# ECUTeen3_5_rev_A_20180306.net
KiCad netlist of a schematic drawn in EAGLE
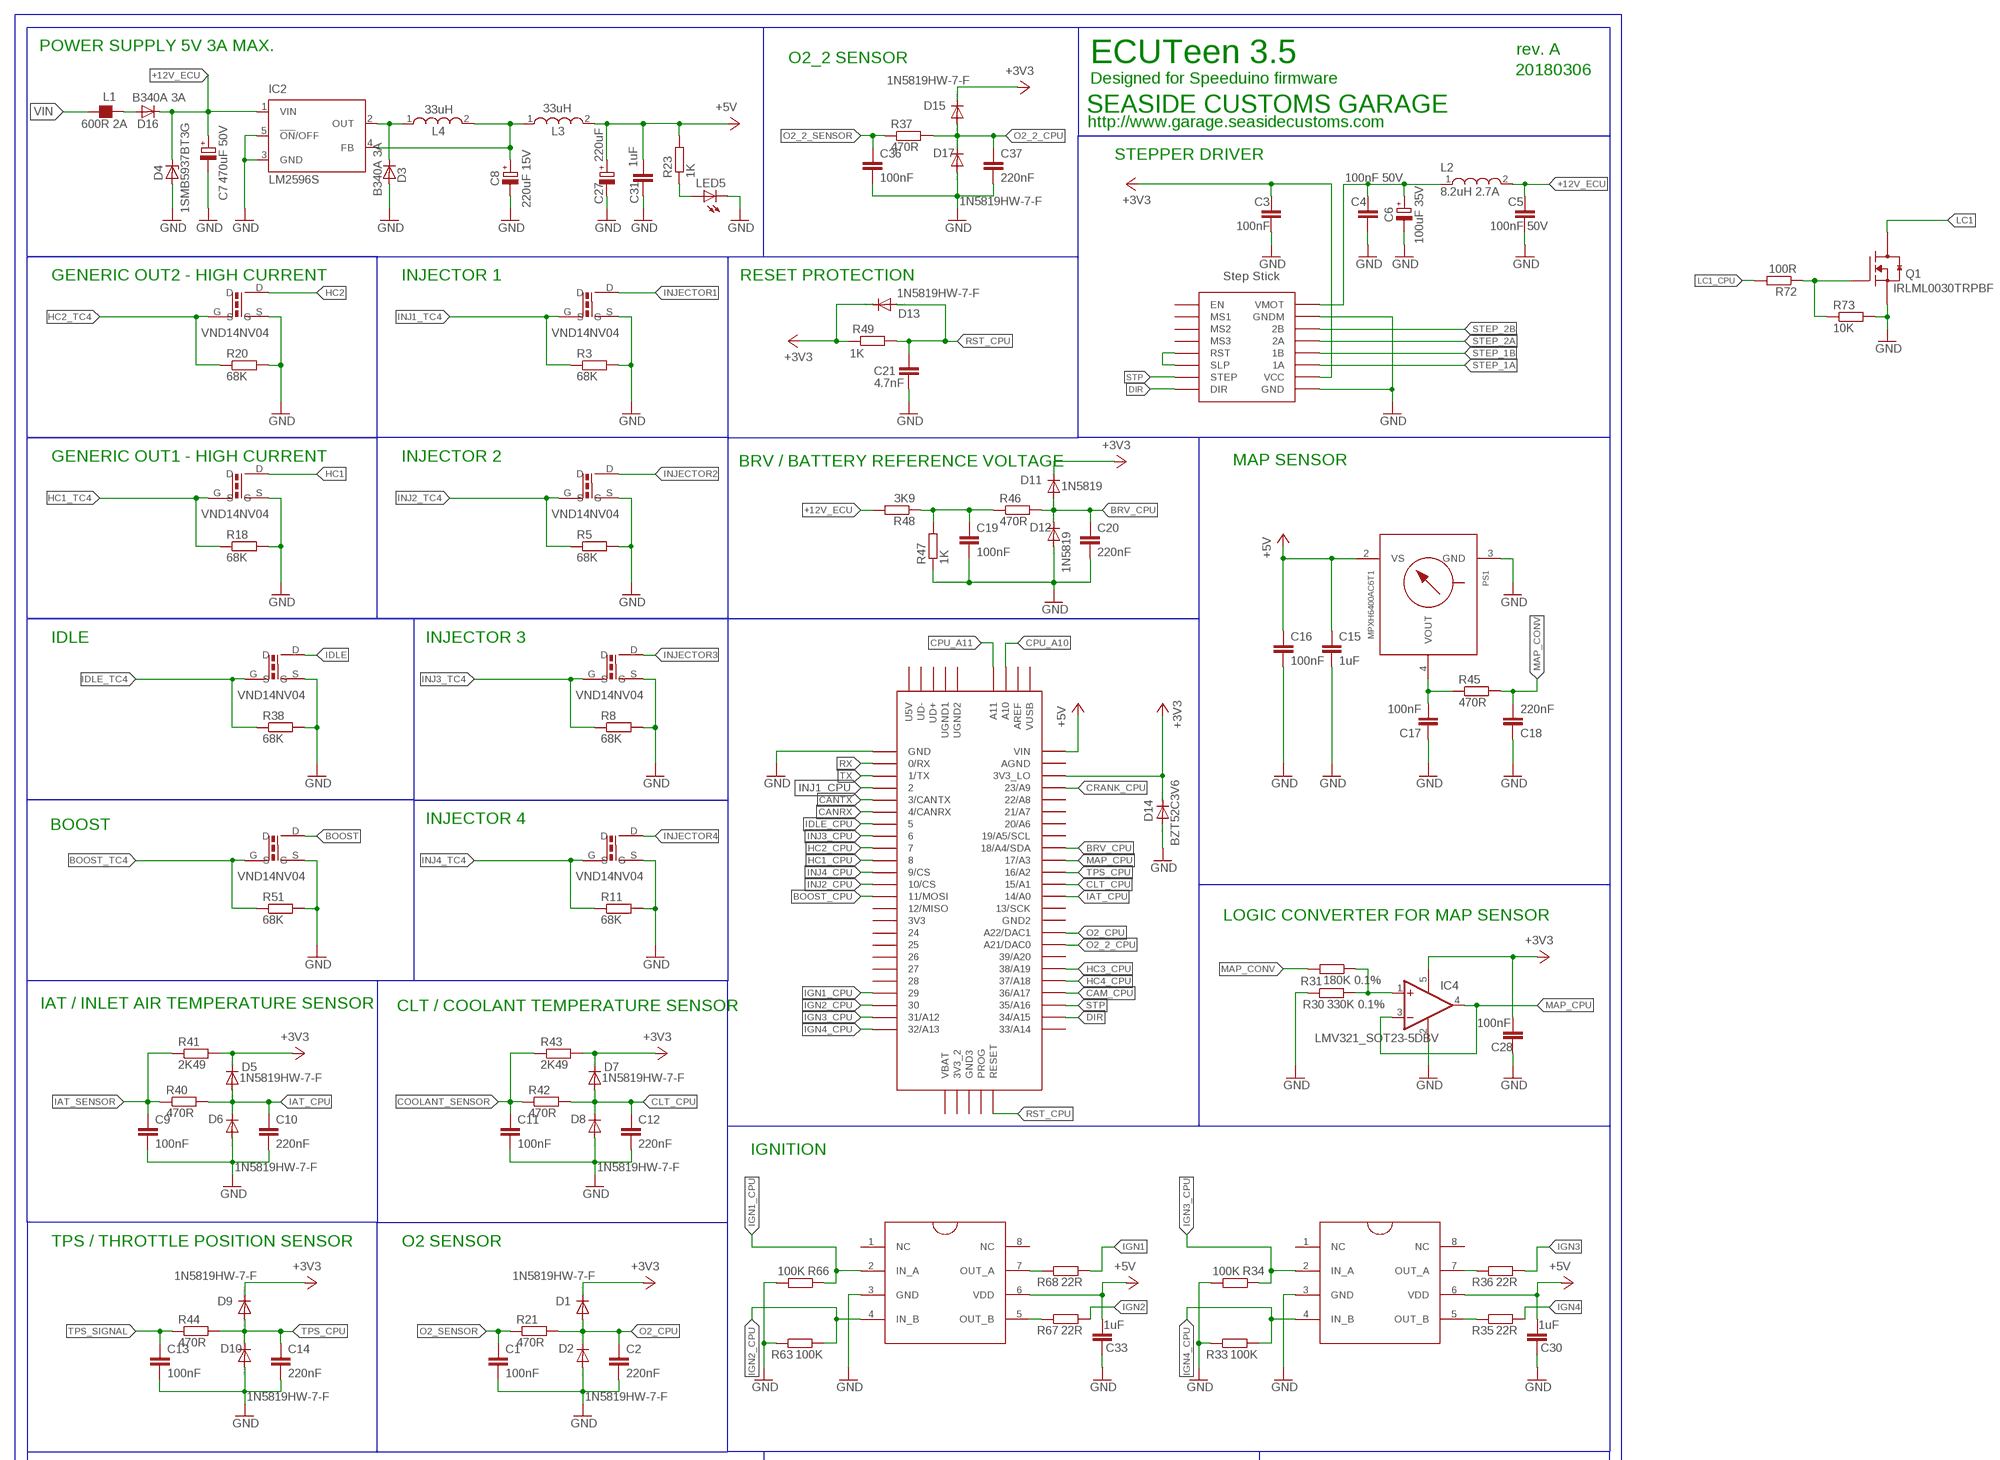
[diagram p0: schematic, sheet 1, part 1 of 2]
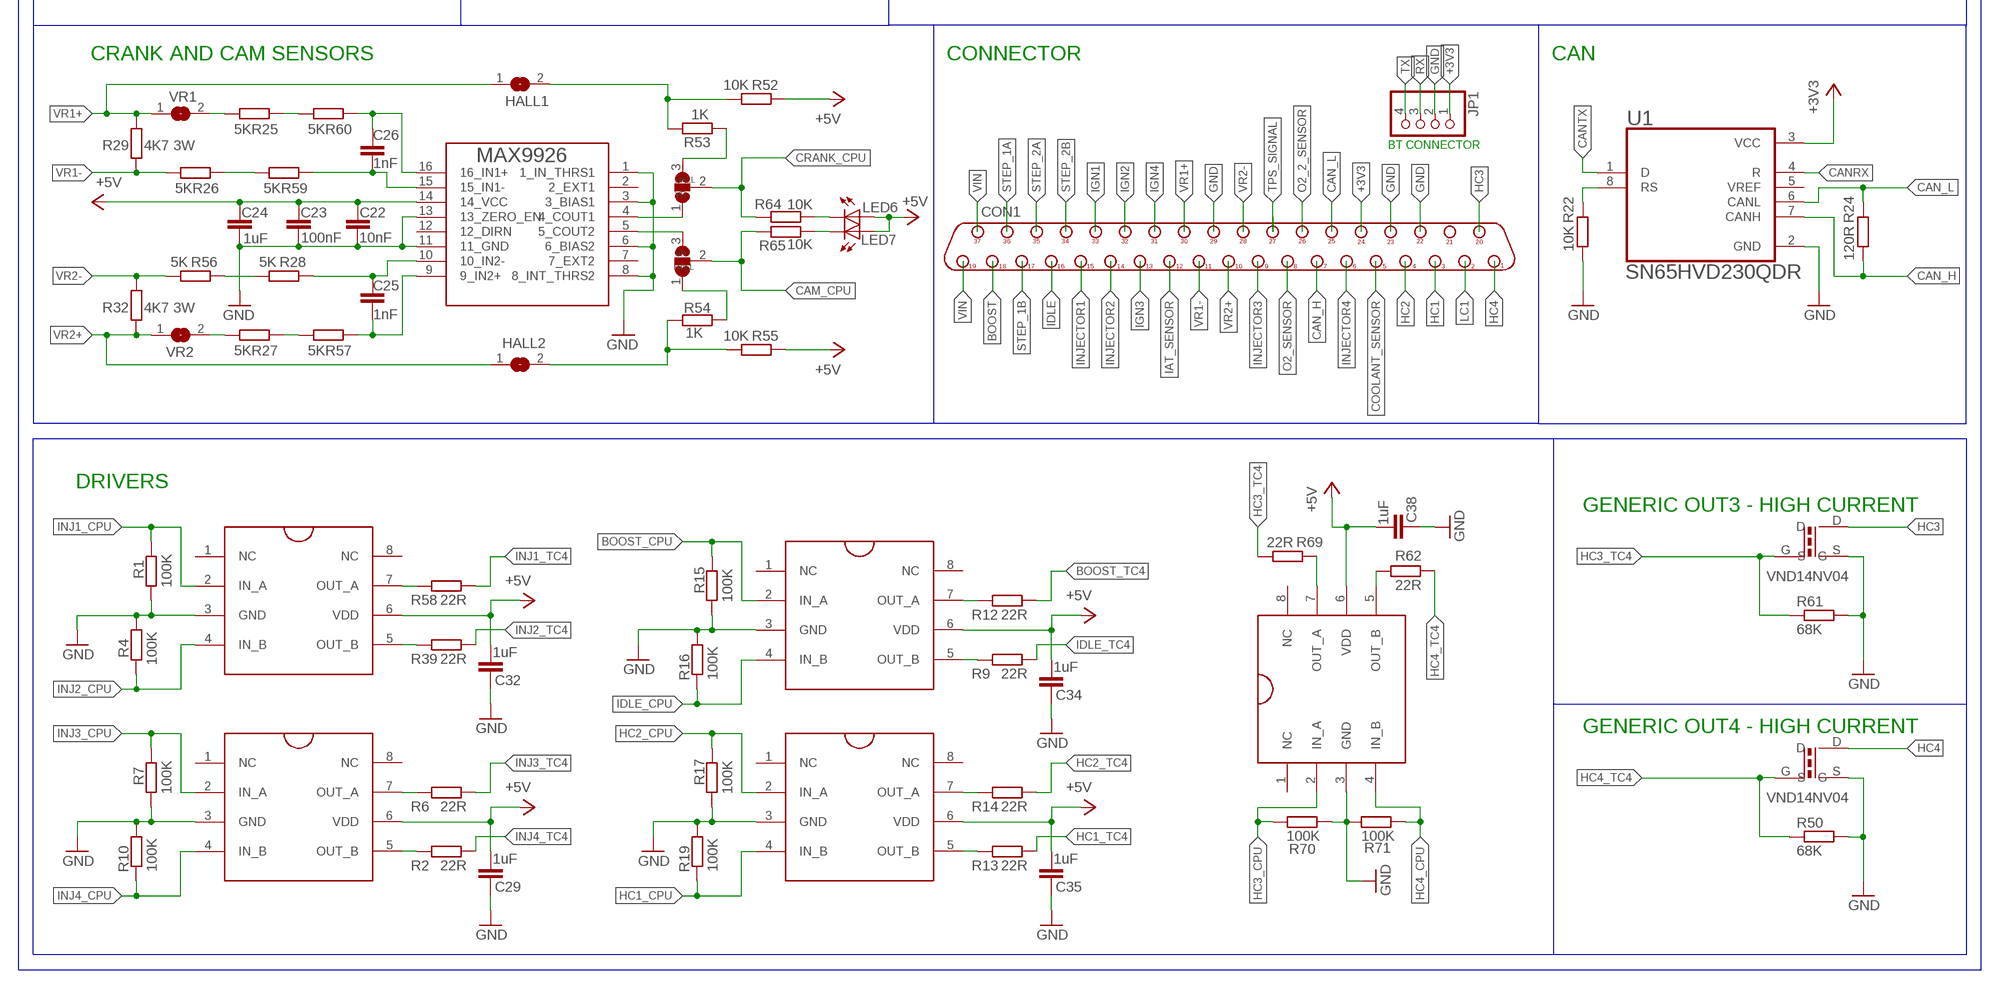
[diagram p1: schematic, sheet 1, part 2 of 2]

(export (version "E")
  (design (tool "Eeschema 10.0.6"))
  (components
    (comp (ref "C1")
      (value "100nF")
      (footprint "eagle-import:C0805")
      (libsource (lib "eagle-import") (part "C-EUC0805"))
    )
    (comp (ref "C2")
      (value "220nF")
      (footprint "eagle-import:C0805")
      (libsource (lib "eagle-import") (part "C-EUC0805"))
    )
    (comp (ref "C3")
      (value "100nF")
      (footprint "eagle-import:C0805")
      (libsource (lib "eagle-import") (part "C-EUC0805"))
    )
    (comp (ref "C4")
      (value "100nF 50V")
      (footprint "eagle-import:C0805")
      (libsource (lib "eagle-import") (part "C-EUC0805"))
    )
    (comp (ref "C5")
      (value "100nF 50V")
      (footprint "eagle-import:C0805")
      (libsource (lib "eagle-import") (part "C-EUC0805"))
    )
    (comp (ref "C6")
      (value "100uF 35V")
      (footprint "eagle-import:PANASONIC_D")
      (libsource (lib "eagle-import") (part "CPOL-EUD"))
    )
    (comp (ref "C7")
      (value "470uF 50V")
      (footprint "eagle-import:PANASONIC_D")
      (libsource (lib "eagle-import") (part "CPOL-EUD"))
    )
    (comp (ref "C8")
      (value "220uF 15V")
      (footprint "eagle-import:PANASONIC_D")
      (libsource (lib "eagle-import") (part "CPOL-EUD"))
    )
    (comp (ref "C9")
      (value "100nF")
      (footprint "eagle-import:C0805")
      (libsource (lib "eagle-import") (part "C-EUC0805"))
    )
    (comp (ref "C10")
      (value "220nF")
      (footprint "eagle-import:C0805")
      (libsource (lib "eagle-import") (part "C-EUC0805"))
    )
    (comp (ref "C11")
      (value "100nF")
      (footprint "eagle-import:C0805")
      (libsource (lib "eagle-import") (part "C-EUC0805"))
    )
    (comp (ref "C12")
      (value "220nF")
      (footprint "eagle-import:C0805")
      (libsource (lib "eagle-import") (part "C-EUC0805"))
    )
    (comp (ref "C13")
      (value "100nF")
      (footprint "eagle-import:C0805")
      (libsource (lib "eagle-import") (part "C-EUC0805"))
    )
    (comp (ref "C14")
      (value "220nF")
      (footprint "eagle-import:C0805")
      (libsource (lib "eagle-import") (part "C-EUC0805"))
    )
    (comp (ref "C15")
      (value "1uF")
      (footprint "eagle-import:C0805")
      (libsource (lib "eagle-import") (part "C-EUC0805"))
    )
    (comp (ref "C16")
      (value "100nF")
      (footprint "eagle-import:C0805")
      (libsource (lib "eagle-import") (part "C-EUC0805"))
    )
    (comp (ref "C17")
      (value "100nF")
      (footprint "eagle-import:C0805")
      (libsource (lib "eagle-import") (part "C-EUC0805"))
    )
    (comp (ref "C18")
      (value "220nF")
      (footprint "eagle-import:C0805")
      (libsource (lib "eagle-import") (part "C-EUC0805"))
    )
    (comp (ref "C19")
      (value "100nF")
      (footprint "eagle-import:C0805")
      (libsource (lib "eagle-import") (part "C-EUC0805"))
    )
    (comp (ref "C20")
      (value "220nF")
      (footprint "eagle-import:C0805")
      (libsource (lib "eagle-import") (part "C-EUC0805"))
    )
    (comp (ref "C21")
      (value "4.7nF")
      (footprint "eagle-import:C0805")
      (libsource (lib "eagle-import") (part "C-EUC0805"))
    )
    (comp (ref "C22")
      (value "10nF")
      (footprint "eagle-import:C0805")
      (libsource (lib "eagle-import") (part "C-EUC0805"))
    )
    (comp (ref "C23")
      (value "100nF")
      (footprint "eagle-import:C0805")
      (libsource (lib "eagle-import") (part "C-EUC0805"))
    )
    (comp (ref "C24")
      (value "1uF")
      (footprint "eagle-import:C0805")
      (libsource (lib "eagle-import") (part "C-EUC0805"))
    )
    (comp (ref "C25")
      (value "1nF")
      (footprint "eagle-import:C0805")
      (libsource (lib "eagle-import") (part "C-EUC0805"))
    )
    (comp (ref "C26")
      (value "1nF")
      (footprint "eagle-import:C0805")
      (libsource (lib "eagle-import") (part "C-EUC0805"))
    )
    (comp (ref "C27")
      (value "220uF")
      (footprint "eagle-import:PANASONIC_D")
      (libsource (lib "eagle-import") (part "CPOL-EUD"))
    )
    (comp (ref "C28")
      (value "100nF")
      (footprint "eagle-import:C0805")
      (libsource (lib "eagle-import") (part "C-EUC0805"))
    )
    (comp (ref "C29")
      (value "1uF")
      (footprint "eagle-import:C0805")
      (libsource (lib "eagle-import") (part "C-EUC0805"))
    )
    (comp (ref "C30")
      (value "1uF")
      (footprint "eagle-import:C0805")
      (libsource (lib "eagle-import") (part "C-EUC0805"))
    )
    (comp (ref "C31")
      (value "1uF")
      (footprint "eagle-import:C0805")
      (libsource (lib "eagle-import") (part "C-EUC0805"))
    )
    (comp (ref "C32")
      (value "1uF")
      (footprint "eagle-import:C0805")
      (libsource (lib "eagle-import") (part "C-EUC0805"))
    )
    (comp (ref "C33")
      (value "1uF")
      (footprint "eagle-import:C0805")
      (libsource (lib "eagle-import") (part "C-EUC0805"))
    )
    (comp (ref "C34")
      (value "1uF")
      (footprint "eagle-import:C0805")
      (libsource (lib "eagle-import") (part "C-EUC0805"))
    )
    (comp (ref "C35")
      (value "1uF")
      (footprint "eagle-import:C0805")
      (libsource (lib "eagle-import") (part "C-EUC0805"))
    )
    (comp (ref "C36")
      (value "100nF")
      (footprint "eagle-import:C0805")
      (libsource (lib "eagle-import") (part "C-EUC0805"))
    )
    (comp (ref "C37")
      (value "220nF")
      (footprint "eagle-import:C0805")
      (libsource (lib "eagle-import") (part "C-EUC0805"))
    )
    (comp (ref "C38")
      (value "1uF")
      (footprint "eagle-import:C0805")
      (libsource (lib "eagle-import") (part "C-EUC0805"))
    )
    (comp (ref "CON1")
      (value "DB37M/90")
      (footprint "eagle-import:D-37M_90")
      (libsource (lib "eagle-import") (part "DB37M/90"))
    )
    (comp (ref "D1")
      (value "1N5819HW-7-F")
      (footprint "eagle-import:SOD123")
      (libsource (lib "eagle-import") (part "diode_DIODE-SOD123"))
    )
    (comp (ref "D2")
      (value "1N5819HW-7-F")
      (footprint "eagle-import:SOD123")
      (libsource (lib "eagle-import") (part "diode_DIODE-SOD123"))
    )
    (comp (ref "D3")
      (value "B340A 3A")
      (footprint "eagle-import:DO214AC")
      (fields (field (name "MF") "Fairchild") (field (name "MPN") "S1A"))
      (libsource (lib "eagle-import") (part "S1A"))
    )
    (comp (ref "D4")
      (value "1SMB5937BT3G")
      (footprint "eagle-import:SMB")
      (libsource (lib "eagle-import") (part "ZENER-DIODESMB"))
    )
    (comp (ref "D5")
      (value "1N5819HW-7-F")
      (footprint "eagle-import:SOD123")
      (libsource (lib "eagle-import") (part "diode_DIODE-SOD123"))
    )
    (comp (ref "D6")
      (value "1N5819HW-7-F")
      (footprint "eagle-import:SOD123")
      (libsource (lib "eagle-import") (part "diode_DIODE-SOD123"))
    )
    (comp (ref "D7")
      (value "1N5819HW-7-F")
      (footprint "eagle-import:SOD123")
      (libsource (lib "eagle-import") (part "diode_DIODE-SOD123"))
    )
    (comp (ref "D8")
      (value "1N5819HW-7-F")
      (footprint "eagle-import:SOD123")
      (libsource (lib "eagle-import") (part "diode_DIODE-SOD123"))
    )
    (comp (ref "D9")
      (value "1N5819HW-7-F")
      (footprint "eagle-import:SOD123")
      (libsource (lib "eagle-import") (part "diode_DIODE-SOD123"))
    )
    (comp (ref "D10")
      (value "1N5819HW-7-F")
      (footprint "eagle-import:SOD123")
      (libsource (lib "eagle-import") (part "diode_DIODE-SOD123"))
    )
    (comp (ref "D11")
      (value "1N5819")
      (footprint "eagle-import:SOD123")
      (libsource (lib "eagle-import") (part "diode_DIODE-SOD123"))
    )
    (comp (ref "D12")
      (value "1N5819")
      (footprint "eagle-import:SOD123")
      (libsource (lib "eagle-import") (part "diode_DIODE-SOD123"))
    )
    (comp (ref "D13")
      (value "1N5819HW-7-F")
      (footprint "eagle-import:SOD123")
      (libsource (lib "eagle-import") (part "diode_DIODE-SOD123"))
    )
    (comp (ref "D14")
      (value "BZT52C3V6")
      (footprint "eagle-import:SOD123")
      (libsource (lib "eagle-import") (part "DIODE-SOD123"))
    )
    (comp (ref "D15")
      (value "1N5819HW-7-F")
      (footprint "eagle-import:SOD123")
      (libsource (lib "eagle-import") (part "diode_DIODE-SOD123"))
    )
    (comp (ref "D16")
      (value "B340A 3A")
      (footprint "eagle-import:DO214AC")
      (fields (field (name "MF") "Fairchild") (field (name "MPN") "S1A"))
      (libsource (lib "eagle-import") (part "S1A"))
    )
    (comp (ref "D17")
      (value "1N5819HW-7-F")
      (footprint "eagle-import:SOD123")
      (libsource (lib "eagle-import") (part "diode_DIODE-SOD123"))
    )
    (comp (ref "IC2")
      (value "LM2596S")
      (footprint "eagle-import:TO263-5")
      (fields (field (name "MF") "NATIONAL SEMICONDUCTOR") (field (name "MPN") "LM2596S-ADJ/NOPB"))
      (libsource (lib "eagle-import") (part "LM2596S"))
    )
    (comp (ref "IC4")
      (value "LMV321_SOT23-5DBV")
      (footprint "eagle-import:SOT23-5")
      (libsource (lib "eagle-import") (part "LMV321_SOT23-5DBV"))
    )
    (comp (ref "JMP1")
      (value "SJ2W")
      (footprint "eagle-import:SJ_2")
      (libsource (lib "eagle-import") (part "SJ2W"))
    )
    (comp (ref "JMP2")
      (value "SJ2W")
      (footprint "eagle-import:SJ_2")
      (libsource (lib "eagle-import") (part "SJ2W"))
    )
    (comp (ref "JP1")
      (value "PINHD-1X4")
      (footprint "eagle-import:1X04")
      (libsource (lib "eagle-import") (part "PINHD-1X4"))
    )
    (comp (ref "L1")
      (value "600R 2A")
      (footprint "eagle-import:L1206")
      (libsource (lib "eagle-import") (part "FB_1206"))
    )
    (comp (ref "L2")
      (value "8.2uH 2.7A")
      (footprint "eagle-import:WE-PD_7332_7345_PLASTIC_BASE")
      (libsource (lib "eagle-import") (part "WE-PD_7332/7345_PLASTIC_BASE"))
    )
    (comp (ref "L3")
      (value "33uH")
      (footprint "eagle-import:WE-LHMI_7030_7050")
      (libsource (lib "eagle-import") (part "WE-LHMI_7030/7050"))
    )
    (comp (ref "L4")
      (value "33uH")
      (footprint "eagle-import:WE-LHMI_7030_7050")
      (libsource (lib "eagle-import") (part "WE-LHMI_7030/7050"))
    )
    (comp (ref "LED5")
      (value "LEDCHIP-LED0805")
      (footprint "eagle-import:CHIP-LED0805")
      (libsource (lib "eagle-import") (part "LEDCHIP-LED0805"))
    )
    (comp (ref "LED6")
      (value "LEDCHIP-LED0805")
      (footprint "eagle-import:CHIP-LED0805")
      (libsource (lib "eagle-import") (part "LEDCHIP-LED0805"))
    )
    (comp (ref "LED7")
      (value "LEDCHIP-LED0805")
      (footprint "eagle-import:CHIP-LED0805")
      (libsource (lib "eagle-import") (part "LEDCHIP-LED0805"))
    )
    (comp (ref "PS1")
      (value "MPXH6400AC6T1")
      (footprint "eagle-import:1317A")
      (libsource (lib "eagle-import") (part "MPXH6400AC6T1"))
    )
    (comp (ref "Q1")
      (value "IRLML0030TRPBF")
      (footprint "eagle-import:SOT95P280X135-3N")
      (libsource (lib "eagle-import") (part "MOSFET-NCH_SOT-23"))
    )
    (comp (ref "R1")
      (value "100K")
      (footprint "eagle-import:R0805")
      (libsource (lib "eagle-import") (part "R-EU_R0805"))
    )
    (comp (ref "R2")
      (value "22R")
      (footprint "eagle-import:R0805")
      (libsource (lib "eagle-import") (part "R-EU_R0805"))
    )
    (comp (ref "R3")
      (value "68K")
      (footprint "eagle-import:R0805")
      (libsource (lib "eagle-import") (part "R-EU_R0805"))
    )
    (comp (ref "R4")
      (value "100K")
      (footprint "eagle-import:R0805")
      (libsource (lib "eagle-import") (part "R-EU_R0805"))
    )
    (comp (ref "R5")
      (value "68K")
      (footprint "eagle-import:R0805")
      (libsource (lib "eagle-import") (part "R-EU_R0805"))
    )
    (comp (ref "R6")
      (value "22R")
      (footprint "eagle-import:R0805")
      (libsource (lib "eagle-import") (part "R-EU_R0805"))
    )
    (comp (ref "R7")
      (value "100K")
      (footprint "eagle-import:R0805")
      (libsource (lib "eagle-import") (part "R-EU_R0805"))
    )
    (comp (ref "R8")
      (value "68K")
      (footprint "eagle-import:R0805")
      (libsource (lib "eagle-import") (part "R-EU_R0805"))
    )
    (comp (ref "R9")
      (value "22R")
      (footprint "eagle-import:R0805")
      (libsource (lib "eagle-import") (part "R-EU_R0805"))
    )
    (comp (ref "R10")
      (value "100K")
      (footprint "eagle-import:R0805")
      (libsource (lib "eagle-import") (part "R-EU_R0805"))
    )
    (comp (ref "R11")
      (value "68K")
      (footprint "eagle-import:R0805")
      (libsource (lib "eagle-import") (part "R-EU_R0805"))
    )
    (comp (ref "R12")
      (value "22R")
      (footprint "eagle-import:R0805")
      (libsource (lib "eagle-import") (part "R-EU_R0805"))
    )
    (comp (ref "R13")
      (value "22R")
      (footprint "eagle-import:R0805")
      (libsource (lib "eagle-import") (part "R-EU_R0805"))
    )
    (comp (ref "R14")
      (value "22R")
      (footprint "eagle-import:R0805")
      (libsource (lib "eagle-import") (part "R-EU_R0805"))
    )
    (comp (ref "R15")
      (value "100K")
      (footprint "eagle-import:R0805")
      (libsource (lib "eagle-import") (part "R-EU_R0805"))
    )
    (comp (ref "R16")
      (value "100K")
      (footprint "eagle-import:R0805")
      (libsource (lib "eagle-import") (part "R-EU_R0805"))
    )
    (comp (ref "R17")
      (value "100K")
      (footprint "eagle-import:R0805")
      (libsource (lib "eagle-import") (part "R-EU_R0805"))
    )
    (comp (ref "R18")
      (value "68K")
      (footprint "eagle-import:R0805")
      (libsource (lib "eagle-import") (part "R-EU_R0805"))
    )
    (comp (ref "R19")
      (value "100K")
      (footprint "eagle-import:R0805")
      (libsource (lib "eagle-import") (part "R-EU_R0805"))
    )
    (comp (ref "R20")
      (value "68K")
      (footprint "eagle-import:R0805")
      (libsource (lib "eagle-import") (part "R-EU_R0805"))
    )
    (comp (ref "R21")
      (value "470R")
      (footprint "eagle-import:R0805")
      (libsource (lib "eagle-import") (part "R-EU_R0805"))
    )
    (comp (ref "R22")
      (value "10K")
      (footprint "eagle-import:R0805")
      (libsource (lib "eagle-import") (part "R-EU_R0805"))
    )
    (comp (ref "R23")
      (value "1K")
      (footprint "eagle-import:R0805")
      (libsource (lib "eagle-import") (part "R-EU_R0805"))
    )
    (comp (ref "R24")
      (value "120R")
      (footprint "eagle-import:R0805")
      (libsource (lib "eagle-import") (part "R-EU_R0805"))
    )
    (comp (ref "R25")
      (value "5K")
      (footprint "eagle-import:R0805")
      (libsource (lib "eagle-import") (part "R-EU_R0805"))
    )
    (comp (ref "R26")
      (value "5K")
      (footprint "eagle-import:R0805")
      (libsource (lib "eagle-import") (part "R-EU_R0805"))
    )
    (comp (ref "R27")
      (value "5K")
      (footprint "eagle-import:R0805")
      (libsource (lib "eagle-import") (part "R-EU_R0805"))
    )
    (comp (ref "R28")
      (value "5K")
      (footprint "eagle-import:R0805")
      (libsource (lib "eagle-import") (part "R-EU_R0805"))
    )
    (comp (ref "R29")
      (value "4K7 3W")
      (footprint "eagle-import:R2512")
      (libsource (lib "eagle-import") (part "R-EU_R2512"))
    )
    (comp (ref "R30")
      (value "330K 0.1%")
      (footprint "eagle-import:R0805")
      (libsource (lib "eagle-import") (part "R-EU_R0805"))
    )
    (comp (ref "R31")
      (value "180K 0.1%")
      (footprint "eagle-import:R0805")
      (libsource (lib "eagle-import") (part "R-EU_R0805"))
    )
    (comp (ref "R32")
      (value "4K7 3W")
      (footprint "eagle-import:R2512")
      (libsource (lib "eagle-import") (part "R-EU_R2512"))
    )
    (comp (ref "R33")
      (value "100K")
      (footprint "eagle-import:R0805")
      (libsource (lib "eagle-import") (part "R-EU_R0805"))
    )
    (comp (ref "R34")
      (value "100K")
      (footprint "eagle-import:R0805")
      (libsource (lib "eagle-import") (part "R-EU_R0805"))
    )
    (comp (ref "R35")
      (value "22R")
      (footprint "eagle-import:M1206")
      (libsource (lib "eagle-import") (part "R-EU_M1206"))
    )
    (comp (ref "R36")
      (value "22R")
      (footprint "eagle-import:M1206")
      (libsource (lib "eagle-import") (part "R-EU_M1206"))
    )
    (comp (ref "R37")
      (value "470R")
      (footprint "eagle-import:R0805")
      (libsource (lib "eagle-import") (part "R-EU_R0805"))
    )
    (comp (ref "R38")
      (value "68K")
      (footprint "eagle-import:R0805")
      (libsource (lib "eagle-import") (part "R-EU_R0805"))
    )
    (comp (ref "R39")
      (value "22R")
      (footprint "eagle-import:R0805")
      (libsource (lib "eagle-import") (part "R-EU_R0805"))
    )
    (comp (ref "R40")
      (value "470R")
      (footprint "eagle-import:R0805")
      (libsource (lib "eagle-import") (part "R-EU_R0805"))
    )
    (comp (ref "R41")
      (value "2K49")
      (footprint "eagle-import:R0805")
      (libsource (lib "eagle-import") (part "R-EU_R0805"))
    )
    (comp (ref "R42")
      (value "470R")
      (footprint "eagle-import:R0805")
      (libsource (lib "eagle-import") (part "R-EU_R0805"))
    )
    (comp (ref "R43")
      (value "2K49")
      (footprint "eagle-import:R0805")
      (libsource (lib "eagle-import") (part "R-EU_R0805"))
    )
    (comp (ref "R44")
      (value "470R")
      (footprint "eagle-import:R0805")
      (libsource (lib "eagle-import") (part "R-EU_R0805"))
    )
    (comp (ref "R45")
      (value "470R")
      (footprint "eagle-import:R0805")
      (libsource (lib "eagle-import") (part "R-EU_R0805"))
    )
    (comp (ref "R46")
      (value "470R")
      (footprint "eagle-import:R0805")
      (libsource (lib "eagle-import") (part "R-EU_R0805"))
    )
    (comp (ref "R47")
      (value "1K")
      (footprint "eagle-import:R0805")
      (libsource (lib "eagle-import") (part "R-EU_R0805"))
    )
    (comp (ref "R48")
      (value "3K9")
      (footprint "eagle-import:R0805")
      (libsource (lib "eagle-import") (part "R-EU_R0805"))
    )
    (comp (ref "R49")
      (value "1K")
      (footprint "eagle-import:R0805")
      (libsource (lib "eagle-import") (part "R-EU_R0805"))
    )
    (comp (ref "R50")
      (value "68K")
      (footprint "eagle-import:R0805")
      (libsource (lib "eagle-import") (part "R-EU_R0805"))
    )
    (comp (ref "R51")
      (value "68K")
      (footprint "eagle-import:R0805")
      (libsource (lib "eagle-import") (part "R-EU_R0805"))
    )
    (comp (ref "R52")
      (value "10K")
      (footprint "eagle-import:R0805")
      (libsource (lib "eagle-import") (part "R-EU_R0805"))
    )
    (comp (ref "R53")
      (value "1K")
      (footprint "eagle-import:R0805")
      (libsource (lib "eagle-import") (part "R-EU_R0805"))
    )
    (comp (ref "R54")
      (value "1K")
      (footprint "eagle-import:R0805")
      (libsource (lib "eagle-import") (part "R-EU_R0805"))
    )
    (comp (ref "R55")
      (value "10K")
      (footprint "eagle-import:R0805")
      (libsource (lib "eagle-import") (part "R-EU_R0805"))
    )
    (comp (ref "R56")
      (value "5K")
      (footprint "eagle-import:R0805")
      (libsource (lib "eagle-import") (part "R-EU_R0805"))
    )
    (comp (ref "R57")
      (value "5K")
      (footprint "eagle-import:R0805")
      (libsource (lib "eagle-import") (part "R-EU_R0805"))
    )
    (comp (ref "R58")
      (value "22R")
      (footprint "eagle-import:R0805")
      (libsource (lib "eagle-import") (part "R-EU_R0805"))
    )
    (comp (ref "R59")
      (value "5K")
      (footprint "eagle-import:R0805")
      (libsource (lib "eagle-import") (part "R-EU_R0805"))
    )
    (comp (ref "R60")
      (value "5K")
      (footprint "eagle-import:R0805")
      (libsource (lib "eagle-import") (part "R-EU_R0805"))
    )
    (comp (ref "R61")
      (value "68K")
      (footprint "eagle-import:R0805")
      (libsource (lib "eagle-import") (part "R-EU_R0805"))
    )
    (comp (ref "R62")
      (value "22R")
      (footprint "eagle-import:R0805")
      (libsource (lib "eagle-import") (part "R-EU_R0805"))
    )
    (comp (ref "R63")
      (value "100K")
      (footprint "eagle-import:R0805")
      (libsource (lib "eagle-import") (part "R-EU_R0805"))
    )
    (comp (ref "R64")
      (value "10K")
      (footprint "eagle-import:R0805")
      (libsource (lib "eagle-import") (part "R-EU_R0805"))
    )
    (comp (ref "R65")
      (value "10K")
      (footprint "eagle-import:R0805")
      (libsource (lib "eagle-import") (part "R-EU_R0805"))
    )
    (comp (ref "R66")
      (value "100K")
      (footprint "eagle-import:R0805")
      (libsource (lib "eagle-import") (part "R-EU_R0805"))
    )
    (comp (ref "R67")
      (value "22R")
      (footprint "eagle-import:M1206")
      (libsource (lib "eagle-import") (part "R-EU_M1206"))
    )
    (comp (ref "R68")
      (value "22R")
      (footprint "eagle-import:M1206")
      (libsource (lib "eagle-import") (part "R-EU_M1206"))
    )
    (comp (ref "R69")
      (value "22R")
      (footprint "eagle-import:R0805")
      (libsource (lib "eagle-import") (part "R-EU_R0805"))
    )
    (comp (ref "R70")
      (value "100K")
      (footprint "eagle-import:R0805")
      (libsource (lib "eagle-import") (part "R-EU_R0805"))
    )
    (comp (ref "R71")
      (value "100K")
      (footprint "eagle-import:R0805")
      (libsource (lib "eagle-import") (part "R-EU_R0805"))
    )
    (comp (ref "R72")
      (value "100R")
      (footprint "eagle-import:R0805")
      (libsource (lib "eagle-import") (part "R-EU_R0805"))
    )
    (comp (ref "R73")
      (value "10K")
      (footprint "eagle-import:R0805")
      (libsource (lib "eagle-import") (part "R-EU_R0805"))
    )
    (comp (ref "SJ3")
      (value "VR2")
      (footprint "eagle-import:SJ")
      (libsource (lib "eagle-import") (part "SJ"))
    )
    (comp (ref "SJ4")
      (value "VR1")
      (footprint "eagle-import:SJ")
      (libsource (lib "eagle-import") (part "SJ"))
    )
    (comp (ref "SJ5")
      (value "HALL2")
      (footprint "eagle-import:SJ")
      (libsource (lib "eagle-import") (part "SJ"))
    )
    (comp (ref "SJ6")
      (value "HALL1")
      (footprint "eagle-import:SJ")
      (libsource (lib "eagle-import") (part "SJ"))
    )
    (comp (ref "STEPSTICK-X")
      (value "STEP-STICK")
      (footprint "eagle-import:STEP-STICK")
      (libsource (lib "eagle-import") (part "STEP-STICK"))
    )
    (comp (ref "U$1")
      (value "TEENSY_3.5/3.6")
      (footprint "eagle-import:TEENSY_3.5_3.6")
      (libsource (lib "eagle-import") (part "TEENSY_3.5/3.6"))
    )
    (comp (ref "U$2")
      (value "DPAK_N-CHANNEL_MOSFET")
      (footprint "eagle-import:DPAK_N-CHANNEL_MOSFET")
      (libsource (lib "eagle-import") (part "DPAK_N-CHANNEL_MOSFET"))
    )
    (comp (ref "U$3")
      (value "DPAK_N-CHANNEL_MOSFET")
      (footprint "eagle-import:DPAK_N-CHANNEL_MOSFET")
      (libsource (lib "eagle-import") (part "DPAK_N-CHANNEL_MOSFET"))
    )
    (comp (ref "U$4")
      (value "DPAK_N-CHANNEL_MOSFET")
      (footprint "eagle-import:DPAK_N-CHANNEL_MOSFET")
      (libsource (lib "eagle-import") (part "DPAK_N-CHANNEL_MOSFET"))
    )
    (comp (ref "U$5")
      (value "DPAK_N-CHANNEL_MOSFET")
      (footprint "eagle-import:DPAK_N-CHANNEL_MOSFET")
      (libsource (lib "eagle-import") (part "DPAK_N-CHANNEL_MOSFET"))
    )
    (comp (ref "U$6")
      (value "DPAK_N-CHANNEL_MOSFET")
      (footprint "eagle-import:DPAK_N-CHANNEL_MOSFET")
      (libsource (lib "eagle-import") (part "DPAK_N-CHANNEL_MOSFET"))
    )
    (comp (ref "U$7")
      (value "TC427SO-8")
      (footprint "eagle-import:SO-8")
      (libsource (lib "eagle-import") (part "TC427SO-8"))
    )
    (comp (ref "U$8")
      (value "DPAK_N-CHANNEL_MOSFET")
      (footprint "eagle-import:DPAK_N-CHANNEL_MOSFET")
      (libsource (lib "eagle-import") (part "DPAK_N-CHANNEL_MOSFET"))
    )
    (comp (ref "U$9")
      (value "TC427SO-8")
      (footprint "eagle-import:SO-8")
      (libsource (lib "eagle-import") (part "TC427SO-8"))
    )
    (comp (ref "U$10")
      (value "MAX9926")
      (footprint "eagle-import:QSOP16")
      (libsource (lib "eagle-import") (part "MAX9926"))
    )
    (comp (ref "U$11")
      (value "TC427SO-8")
      (footprint "eagle-import:SO-8")
      (libsource (lib "eagle-import") (part "TC427SO-8"))
    )
    (comp (ref "U$12")
      (value "DPAK_N-CHANNEL_MOSFET")
      (footprint "eagle-import:DPAK_N-CHANNEL_MOSFET")
      (libsource (lib "eagle-import") (part "DPAK_N-CHANNEL_MOSFET"))
    )
    (comp (ref "U$13")
      (value "DPAK_N-CHANNEL_MOSFET")
      (footprint "eagle-import:DPAK_N-CHANNEL_MOSFET")
      (libsource (lib "eagle-import") (part "DPAK_N-CHANNEL_MOSFET"))
    )
    (comp (ref "U$14")
      (value "TC427SO-8")
      (footprint "eagle-import:SO-8")
      (libsource (lib "eagle-import") (part "TC427SO-8"))
    )
    (comp (ref "U$15")
      (value "TC427SO-8")
      (footprint "eagle-import:SO-8")
      (libsource (lib "eagle-import") (part "TC427SO-8"))
    )
    (comp (ref "U$16")
      (value "TC427SO-8")
      (footprint "eagle-import:SO-8")
      (libsource (lib "eagle-import") (part "TC427SO-8"))
    )
    (comp (ref "U$17")
      (value "DPAK_N-CHANNEL_MOSFET")
      (footprint "eagle-import:DPAK_N-CHANNEL_MOSFET")
      (libsource (lib "eagle-import") (part "DPAK_N-CHANNEL_MOSFET"))
    )
    (comp (ref "U$18")
      (value "DPAK_N-CHANNEL_MOSFET")
      (footprint "eagle-import:DPAK_N-CHANNEL_MOSFET")
      (libsource (lib "eagle-import") (part "DPAK_N-CHANNEL_MOSFET"))
    )
    (comp (ref "U$19")
      (value "TC427SO-8")
      (footprint "eagle-import:SO-8")
      (libsource (lib "eagle-import") (part "TC427SO-8"))
    )
    (comp (ref "U1")
      (value "SN65HVD230QDR")
      (footprint "eagle-import:SOIC127P600X175-8N")
      (fields (field (name "MF") "Texas Instruments"))
      (libsource (lib "eagle-import") (part "SN65HVD230QDR"))
    )
  )
  (nets
    (net (code "2") (name "+3V3") (class "Default")
      (node (ref "C28") (pin "2") (pinfunction "2_2") (pintype "passive"))
      (node (ref "C3") (pin "1") (pinfunction "1_1") (pintype "passive"))
      (node (ref "CON1") (pin "24") (pinfunction "24_24") (pintype "passive"))
      (node (ref "D1") (pin "C") (pinfunction "C_C") (pintype "passive"))
      (node (ref "D11") (pin "C") (pinfunction "C_C") (pintype "passive"))
      (node (ref "D13") (pin "C") (pinfunction "C_C") (pintype "passive"))
      (node (ref "D14") (pin "C") (pinfunction "C_C") (pintype "passive"))
      (node (ref "D15") (pin "C") (pinfunction "C_C") (pintype "passive"))
      (node (ref "D5") (pin "C") (pinfunction "C_C") (pintype "passive"))
      (node (ref "D7") (pin "C") (pinfunction "C_C") (pintype "passive"))
      (node (ref "D9") (pin "C") (pinfunction "C_C") (pintype "passive"))
      (node (ref "IC4") (pin "5") (pinfunction "V+_5") (pintype "power_in"))
      (node (ref "JP1") (pin "1") (pinfunction "1_1") (pintype "passive"))
      (node (ref "R41") (pin "2") (pinfunction "2_2") (pintype "passive"))
      (node (ref "R43") (pin "2") (pinfunction "2_2") (pintype "passive"))
      (node (ref "R49") (pin "1") (pinfunction "1_1") (pintype "passive"))
      (node (ref "STEPSTICK-X") (pin "VCC") (pinfunction "VCC_VCC") (pintype "bidirectional"))
      (node (ref "U$1") (pin "3V3_LO") (pinfunction "3V3_LO_3V3_LO") (pintype "bidirectional"))
      (node (ref "U1") (pin "3") (pinfunction "VCC_3") (pintype "power_in"))
    )
    (net (code "3") (name "+5V") (class "Default")
      (node (ref "C15") (pin "1") (pinfunction "1_1") (pintype "passive"))
      (node (ref "C16") (pin "1") (pinfunction "1_1") (pintype "passive"))
      (node (ref "C22") (pin "1") (pinfunction "1_1") (pintype "passive"))
      (node (ref "C23") (pin "1") (pinfunction "1_1") (pintype "passive"))
      (node (ref "C24") (pin "1") (pinfunction "1_1") (pintype "passive"))
      (node (ref "C27") (pin "+") (pinfunction "+_+") (pintype "passive"))
      (node (ref "C29") (pin "2") (pinfunction "2_2") (pintype "passive"))
      (node (ref "C30") (pin "2") (pinfunction "2_2") (pintype "passive"))
      (node (ref "C31") (pin "1") (pinfunction "1_1") (pintype "passive"))
      (node (ref "C32") (pin "2") (pinfunction "2_2") (pintype "passive"))
      (node (ref "C33") (pin "2") (pinfunction "2_2") (pintype "passive"))
      (node (ref "C34") (pin "2") (pinfunction "2_2") (pintype "passive"))
      (node (ref "C35") (pin "2") (pinfunction "2_2") (pintype "passive"))
      (node (ref "C38") (pin "2") (pinfunction "2_2") (pintype "passive"))
      (node (ref "L3") (pin "2") (pinfunction "2_2") (pintype "passive"))
      (node (ref "LED6") (pin "A") (pinfunction "A_A") (pintype "passive"))
      (node (ref "LED7") (pin "A") (pinfunction "A_A") (pintype "passive"))
      (node (ref "PS1") (pin "2") (pinfunction "VS_2") (pintype "power_in"))
      (node (ref "R23") (pin "2") (pinfunction "2_2") (pintype "passive"))
      (node (ref "R52") (pin "1") (pinfunction "1_1") (pintype "passive"))
      (node (ref "R55") (pin "1") (pinfunction "1_1") (pintype "passive"))
      (node (ref "U$1") (pin "VIN") (pinfunction "VIN_VIN") (pintype "bidirectional"))
      (node (ref "U$10") (pin "14") (pinfunction "14_VCC_14") (pintype "bidirectional"))
      (node (ref "U$11") (pin "6") (pinfunction "VDD_6") (pintype "power_in"))
      (node (ref "U$14") (pin "6") (pinfunction "VDD_6") (pintype "power_in"))
      (node (ref "U$15") (pin "6") (pinfunction "VDD_6") (pintype "power_in"))
      (node (ref "U$16") (pin "6") (pinfunction "VDD_6") (pintype "power_in"))
      (node (ref "U$19") (pin "6") (pinfunction "VDD_6") (pintype "power_in"))
      (node (ref "U$7") (pin "6") (pinfunction "VDD_6") (pintype "power_in"))
      (node (ref "U$9") (pin "6") (pinfunction "VDD_6") (pintype "power_in"))
    )
    (net (code "4") (name "+12V_ECU") (class "Default")
      (node (ref "C5") (pin "1") (pinfunction "1_1") (pintype "passive"))
      (node (ref "C7") (pin "+") (pinfunction "+_+") (pintype "passive"))
      (node (ref "D16") (pin "C") (pinfunction "C_C") (pintype "passive"))
      (node (ref "D4") (pin "C") (pinfunction "C_C") (pintype "passive"))
      (node (ref "IC2") (pin "1") (pinfunction "VIN_1") (pintype "input"))
      (node (ref "L2") (pin "2") (pinfunction "2_2") (pintype "passive"))
      (node (ref "R48") (pin "2") (pinfunction "2_2") (pintype "passive"))
    )
    (net (code "6") (name "BOOST") (class "Default")
      (node (ref "CON1") (pin "18") (pinfunction "18_18") (pintype "passive"))
      (node (ref "U$13") (pin "D") (pinfunction "D_D") (pintype "bidirectional"))
    )
    (net (code "7") (name "BOOST_CPU") (class "Default")
      (node (ref "R15") (pin "2") (pinfunction "2_2") (pintype "passive"))
      (node (ref "U$1") (pin "11/MOSI") (pinfunction "11/MOSI_11/MOSI") (pintype "bidirectional"))
      (node (ref "U$15") (pin "2") (pinfunction "IN_A_2") (pintype "input"))
    )
    (net (code "8") (name "BOOST_TC4") (class "Default")
      (node (ref "R12") (pin "2") (pinfunction "2_2") (pintype "passive"))
      (node (ref "R51") (pin "1") (pinfunction "1_1") (pintype "passive"))
      (node (ref "U$13") (pin "G") (pinfunction "G_G") (pintype "bidirectional"))
    )
    (net (code "9") (name "BRV_CPU") (class "Default")
      (node (ref "C20") (pin "1") (pinfunction "1_1") (pintype "passive"))
      (node (ref "D11") (pin "A") (pinfunction "A_A") (pintype "passive"))
      (node (ref "D12") (pin "C") (pinfunction "C_C") (pintype "passive"))
      (node (ref "R46") (pin "2") (pinfunction "2_2") (pintype "passive"))
      (node (ref "U$1") (pin "18/A4/SDA") (pinfunction "18/A4/SDA_18/A4/SDA") (pintype "bidirectional"))
    )
    (net (code "10") (name "CAM_CPU") (class "Default")
      (node (ref "JMP2") (pin "2") (pinfunction "2_2") (pintype "passive"))
      (node (ref "R65") (pin "1") (pinfunction "1_1") (pintype "passive"))
      (node (ref "U$1") (pin "36/A17") (pinfunction "36/A17_36/A17") (pintype "bidirectional"))
    )
    (net (code "11") (name "CANRX") (class "Default")
      (node (ref "U$1") (pin "4/CANRX") (pinfunction "4/CANRX_4/CANRX") (pintype "bidirectional"))
      (node (ref "U1") (pin "4") (pinfunction "R_4") (pintype "output"))
    )
    (net (code "12") (name "CANTX") (class "Default")
      (node (ref "U$1") (pin "3/CANTX") (pinfunction "3/CANTX_3/CANTX") (pintype "bidirectional"))
      (node (ref "U1") (pin "1") (pinfunction "D_1") (pintype "input"))
    )
    (net (code "13") (name "CAN_H") (class "Default")
      (node (ref "CON1") (pin "7") (pinfunction "7_7") (pintype "passive"))
      (node (ref "R24") (pin "2") (pinfunction "2_2") (pintype "passive"))
      (node (ref "U1") (pin "7") (pinfunction "CANH_7") (pintype "output"))
    )
    (net (code "14") (name "CAN_L") (class "Default")
      (node (ref "CON1") (pin "25") (pinfunction "25_25") (pintype "passive"))
      (node (ref "R24") (pin "1") (pinfunction "1_1") (pintype "passive"))
      (node (ref "U1") (pin "6") (pinfunction "CANL_6") (pintype "output"))
    )
    (net (code "15") (name "CLT_CPU") (class "Default")
      (node (ref "C12") (pin "1") (pinfunction "1_1") (pintype "passive"))
      (node (ref "D7") (pin "A") (pinfunction "A_A") (pintype "passive"))
      (node (ref "D8") (pin "C") (pinfunction "C_C") (pintype "passive"))
      (node (ref "R42") (pin "2") (pinfunction "2_2") (pintype "passive"))
      (node (ref "U$1") (pin "15/A1") (pinfunction "15/A1_15/A1") (pintype "bidirectional"))
    )
    (net (code "16") (name "COOLANT_SENSOR") (class "Default")
      (node (ref "C11") (pin "1") (pinfunction "1_1") (pintype "passive"))
      (node (ref "CON1") (pin "5") (pinfunction "5_5") (pintype "passive"))
      (node (ref "R42") (pin "1") (pinfunction "1_1") (pintype "passive"))
      (node (ref "R43") (pin "1") (pinfunction "1_1") (pintype "passive"))
    )
    (net (code "17") (name "CPU_A10") (class "Default")
      (node (ref "U$1") (pin "A10") (pinfunction "A10_A10") (pintype "bidirectional"))
    )
    (net (code "18") (name "CPU_A11") (class "Default")
      (node (ref "U$1") (pin "A11") (pinfunction "A11_A11") (pintype "bidirectional"))
    )
    (net (code "19") (name "CRANK_CPU") (class "Default")
      (node (ref "JMP1") (pin "2") (pinfunction "2_2") (pintype "passive"))
      (node (ref "R64") (pin "1") (pinfunction "1_1") (pintype "passive"))
      (node (ref "U$1") (pin "23/A9") (pinfunction "23/A9_23/A9") (pintype "bidirectional"))
    )
    (net (code "20") (name "DIR") (class "Default")
      (node (ref "STEPSTICK-X") (pin "DIR") (pinfunction "DIR_DIR") (pintype "bidirectional"))
      (node (ref "U$1") (pin "34/A15") (pinfunction "34/A15_34/A15") (pintype "bidirectional"))
    )
    (net (code "21") (name "GND") (class "Default")
      (node (ref "C1") (pin "2") (pinfunction "2_2") (pintype "passive"))
      (node (ref "C10") (pin "2") (pinfunction "2_2") (pintype "passive"))
      (node (ref "C11") (pin "2") (pinfunction "2_2") (pintype "passive"))
      (node (ref "C12") (pin "2") (pinfunction "2_2") (pintype "passive"))
      (node (ref "C13") (pin "2") (pinfunction "2_2") (pintype "passive"))
      (node (ref "C14") (pin "2") (pinfunction "2_2") (pintype "passive"))
      (node (ref "C15") (pin "2") (pinfunction "2_2") (pintype "passive"))
      (node (ref "C16") (pin "2") (pinfunction "2_2") (pintype "passive"))
      (node (ref "C17") (pin "1") (pinfunction "1_1") (pintype "passive"))
      (node (ref "C18") (pin "1") (pinfunction "1_1") (pintype "passive"))
      (node (ref "C19") (pin "2") (pinfunction "2_2") (pintype "passive"))
      (node (ref "C2") (pin "2") (pinfunction "2_2") (pintype "passive"))
      (node (ref "C20") (pin "2") (pinfunction "2_2") (pintype "passive"))
      (node (ref "C21") (pin "2") (pinfunction "2_2") (pintype "passive"))
      (node (ref "C22") (pin "2") (pinfunction "2_2") (pintype "passive"))
      (node (ref "C23") (pin "2") (pinfunction "2_2") (pintype "passive"))
      (node (ref "C24") (pin "2") (pinfunction "2_2") (pintype "passive"))
      (node (ref "C27") (pin "-") (pinfunction "-_-") (pintype "passive"))
      (node (ref "C28") (pin "1") (pinfunction "1_1") (pintype "passive"))
      (node (ref "C29") (pin "1") (pinfunction "1_1") (pintype "passive"))
      (node (ref "C3") (pin "2") (pinfunction "2_2") (pintype "passive"))
      (node (ref "C30") (pin "1") (pinfunction "1_1") (pintype "passive"))
      (node (ref "C31") (pin "2") (pinfunction "2_2") (pintype "passive"))
      (node (ref "C32") (pin "1") (pinfunction "1_1") (pintype "passive"))
      (node (ref "C33") (pin "1") (pinfunction "1_1") (pintype "passive"))
      (node (ref "C34") (pin "1") (pinfunction "1_1") (pintype "passive"))
      (node (ref "C35") (pin "1") (pinfunction "1_1") (pintype "passive"))
      (node (ref "C36") (pin "2") (pinfunction "2_2") (pintype "passive"))
      (node (ref "C37") (pin "2") (pinfunction "2_2") (pintype "passive"))
      (node (ref "C38") (pin "1") (pinfunction "1_1") (pintype "passive"))
      (node (ref "C4") (pin "2") (pinfunction "2_2") (pintype "passive"))
      (node (ref "C5") (pin "2") (pinfunction "2_2") (pintype "passive"))
      (node (ref "C6") (pin "-") (pinfunction "-_-") (pintype "passive"))
      (node (ref "C7") (pin "-") (pinfunction "-_-") (pintype "passive"))
      (node (ref "C8") (pin "-") (pinfunction "-_-") (pintype "passive"))
      (node (ref "C9") (pin "2") (pinfunction "2_2") (pintype "passive"))
      (node (ref "CON1") (pin "22") (pinfunction "22_22") (pintype "passive"))
      (node (ref "CON1") (pin "23") (pinfunction "23_23") (pintype "passive"))
      (node (ref "CON1") (pin "29") (pinfunction "29_29") (pintype "passive"))
      (node (ref "D10") (pin "A") (pinfunction "A_A") (pintype "passive"))
      (node (ref "D12") (pin "A") (pinfunction "A_A") (pintype "passive"))
      (node (ref "D14") (pin "A") (pinfunction "A_A") (pintype "passive"))
      (node (ref "D17") (pin "A") (pinfunction "A_A") (pintype "passive"))
      (node (ref "D2") (pin "A") (pinfunction "A_A") (pintype "passive"))
      (node (ref "D3") (pin "A") (pinfunction "A_A") (pintype "passive"))
      (node (ref "D4") (pin "A") (pinfunction "A_A") (pintype "passive"))
      (node (ref "D6") (pin "A") (pinfunction "A_A") (pintype "passive"))
      (node (ref "D8") (pin "A") (pinfunction "A_A") (pintype "passive"))
      (node (ref "IC2") (pin "3") (pinfunction "GND_3") (pintype "power_in"))
      (node (ref "IC2") (pin "5") (pinfunction "~{ON}/OFF_5") (pintype "input"))
      (node (ref "IC4") (pin "2") (pinfunction "V-_2") (pintype "power_in"))
      (node (ref "JP1") (pin "2") (pinfunction "2_2") (pintype "passive"))
      (node (ref "LED5") (pin "C") (pinfunction "C_C") (pintype "passive"))
      (node (ref "PS1") (pin "3") (pinfunction "GND_3") (pintype "power_in"))
      (node (ref "Q1") (pin "2") (pinfunction "S_2") (pintype "passive"))
      (node (ref "R1") (pin "1") (pinfunction "1_1") (pintype "passive"))
      (node (ref "R10") (pin "1") (pinfunction "1_1") (pintype "passive"))
      (node (ref "R11") (pin "2") (pinfunction "2_2") (pintype "passive"))
      (node (ref "R15") (pin "1") (pinfunction "1_1") (pintype "passive"))
      (node (ref "R16") (pin "1") (pinfunction "1_1") (pintype "passive"))
      (node (ref "R17") (pin "1") (pinfunction "1_1") (pintype "passive"))
      (node (ref "R18") (pin "2") (pinfunction "2_2") (pintype "passive"))
      (node (ref "R19") (pin "1") (pinfunction "1_1") (pintype "passive"))
      (node (ref "R20") (pin "2") (pinfunction "2_2") (pintype "passive"))
      (node (ref "R22") (pin "2") (pinfunction "2_2") (pintype "passive"))
      (node (ref "R3") (pin "2") (pinfunction "2_2") (pintype "passive"))
      (node (ref "R30") (pin "1") (pinfunction "1_1") (pintype "passive"))
      (node (ref "R33") (pin "1") (pinfunction "1_1") (pintype "passive"))
      (node (ref "R34") (pin "2") (pinfunction "2_2") (pintype "passive"))
      (node (ref "R38") (pin "2") (pinfunction "2_2") (pintype "passive"))
      (node (ref "R4") (pin "1") (pinfunction "1_1") (pintype "passive"))
      (node (ref "R47") (pin "1") (pinfunction "1_1") (pintype "passive"))
      (node (ref "R5") (pin "2") (pinfunction "2_2") (pintype "passive"))
      (node (ref "R50") (pin "2") (pinfunction "2_2") (pintype "passive"))
      (node (ref "R51") (pin "2") (pinfunction "2_2") (pintype "passive"))
      (node (ref "R61") (pin "2") (pinfunction "2_2") (pintype "passive"))
      (node (ref "R63") (pin "1") (pinfunction "1_1") (pintype "passive"))
      (node (ref "R66") (pin "2") (pinfunction "2_2") (pintype "passive"))
      (node (ref "R7") (pin "1") (pinfunction "1_1") (pintype "passive"))
      (node (ref "R70") (pin "1") (pinfunction "1_1") (pintype "passive"))
      (node (ref "R71") (pin "1") (pinfunction "1_1") (pintype "passive"))
      (node (ref "R73") (pin "2") (pinfunction "2_2") (pintype "passive"))
      (node (ref "R8") (pin "2") (pinfunction "2_2") (pintype "passive"))
      (node (ref "STEPSTICK-X") (pin "GND") (pinfunction "GND_GND") (pintype "bidirectional"))
      (node (ref "STEPSTICK-X") (pin "GNDM") (pinfunction "GNDM_GNDM") (pintype "bidirectional"))
      (node (ref "U$1") (pin "GND") (pinfunction "GND_GND") (pintype "bidirectional"))
      (node (ref "U$10") (pin "1") (pinfunction "1_IN_THRS1_1") (pintype "bidirectional"))
      (node (ref "U$10") (pin "11") (pinfunction "11_GND_11") (pintype "bidirectional"))
      (node (ref "U$10") (pin "13") (pinfunction "13_ZERO_EN_13") (pintype "bidirectional"))
      (node (ref "U$10") (pin "3") (pinfunction "3_BIAS1_3") (pintype "bidirectional"))
      (node (ref "U$10") (pin "6") (pinfunction "6_BIAS2_6") (pintype "bidirectional"))
      (node (ref "U$10") (pin "8") (pinfunction "8_INT_THRS2_8") (pintype "bidirectional"))
      (node (ref "U$11") (pin "3") (pinfunction "GND_3") (pintype "power_in"))
      (node (ref "U$12") (pin "S") (pinfunction "S_S") (pintype "bidirectional"))
      (node (ref "U$13") (pin "S") (pinfunction "S_S") (pintype "bidirectional"))
      (node (ref "U$14") (pin "3") (pinfunction "GND_3") (pintype "power_in"))
      (node (ref "U$15") (pin "3") (pinfunction "GND_3") (pintype "power_in"))
      (node (ref "U$16") (pin "3") (pinfunction "GND_3") (pintype "power_in"))
      (node (ref "U$17") (pin "S") (pinfunction "S_S") (pintype "bidirectional"))
      (node (ref "U$18") (pin "S") (pinfunction "S_S") (pintype "bidirectional"))
      (node (ref "U$19") (pin "3") (pinfunction "GND_3") (pintype "power_in"))
      (node (ref "U$2") (pin "S") (pinfunction "S_S") (pintype "bidirectional"))
      (node (ref "U$3") (pin "S") (pinfunction "S_S") (pintype "bidirectional"))
      (node (ref "U$4") (pin "S") (pinfunction "S_S") (pintype "bidirectional"))
      (node (ref "U$5") (pin "S") (pinfunction "S_S") (pintype "bidirectional"))
      (node (ref "U$6") (pin "S") (pinfunction "S_S") (pintype "bidirectional"))
      (node (ref "U$7") (pin "3") (pinfunction "GND_3") (pintype "power_in"))
      (node (ref "U$8") (pin "S") (pinfunction "S_S") (pintype "bidirectional"))
      (node (ref "U$9") (pin "3") (pinfunction "GND_3") (pintype "power_in"))
      (node (ref "U1") (pin "2") (pinfunction "GND_2") (pintype "power_in"))
    )
    (net (code "22") (name "HC1") (class "Default")
      (node (ref "CON1") (pin "3") (pinfunction "3_3") (pintype "passive"))
      (node (ref "U$3") (pin "D") (pinfunction "D_D") (pintype "bidirectional"))
    )
    (net (code "23") (name "HC1_CPU") (class "Default")
      (node (ref "R19") (pin "2") (pinfunction "2_2") (pintype "passive"))
      (node (ref "U$1") (pin "8") (pinfunction "8_8") (pintype "bidirectional"))
      (node (ref "U$16") (pin "4") (pinfunction "IN_B_4") (pintype "input"))
    )
    (net (code "24") (name "HC1_TC4") (class "Default")
      (node (ref "R13") (pin "2") (pinfunction "2_2") (pintype "passive"))
      (node (ref "R18") (pin "1") (pinfunction "1_1") (pintype "passive"))
      (node (ref "U$3") (pin "G") (pinfunction "G_G") (pintype "bidirectional"))
    )
    (net (code "25") (name "HC2") (class "Default")
      (node (ref "CON1") (pin "4") (pinfunction "4_4") (pintype "passive"))
      (node (ref "U$2") (pin "D") (pinfunction "D_D") (pintype "bidirectional"))
    )
    (net (code "26") (name "HC2_CPU") (class "Default")
      (node (ref "R17") (pin "2") (pinfunction "2_2") (pintype "passive"))
      (node (ref "U$1") (pin "7") (pinfunction "7_7") (pintype "bidirectional"))
      (node (ref "U$16") (pin "2") (pinfunction "IN_A_2") (pintype "input"))
    )
    (net (code "27") (name "HC2_TC4") (class "Default")
      (node (ref "R14") (pin "2") (pinfunction "2_2") (pintype "passive"))
      (node (ref "R20") (pin "1") (pinfunction "1_1") (pintype "passive"))
      (node (ref "U$2") (pin "G") (pinfunction "G_G") (pintype "bidirectional"))
    )
    (net (code "28") (name "HC3") (class "Default")
      (node (ref "CON1") (pin "20") (pinfunction "20_20") (pintype "passive"))
      (node (ref "U$17") (pin "D") (pinfunction "D_D") (pintype "bidirectional"))
    )
    (net (code "29") (name "HC3_CPU") (class "Default")
      (node (ref "R70") (pin "2") (pinfunction "2_2") (pintype "passive"))
      (node (ref "U$1") (pin "38/A19") (pinfunction "38/A19_38/A19") (pintype "bidirectional"))
      (node (ref "U$19") (pin "2") (pinfunction "IN_A_2") (pintype "input"))
    )
    (net (code "30") (name "HC3_TC4") (class "Default")
      (node (ref "R61") (pin "1") (pinfunction "1_1") (pintype "passive"))
      (node (ref "R69") (pin "2") (pinfunction "2_2") (pintype "passive"))
      (node (ref "U$17") (pin "G") (pinfunction "G_G") (pintype "bidirectional"))
    )
    (net (code "31") (name "HC4") (class "Default")
      (node (ref "CON1") (pin "1") (pinfunction "1_1") (pintype "passive"))
      (node (ref "U$18") (pin "D") (pinfunction "D_D") (pintype "bidirectional"))
    )
    (net (code "32") (name "HC4_CPU") (class "Default")
      (node (ref "R71") (pin "2") (pinfunction "2_2") (pintype "passive"))
      (node (ref "U$1") (pin "37/A18") (pinfunction "37/A18_37/A18") (pintype "bidirectional"))
      (node (ref "U$19") (pin "4") (pinfunction "IN_B_4") (pintype "input"))
    )
    (net (code "33") (name "HC4_TC4") (class "Default")
      (node (ref "R50") (pin "1") (pinfunction "1_1") (pintype "passive"))
      (node (ref "R62") (pin "2") (pinfunction "2_2") (pintype "passive"))
      (node (ref "U$18") (pin "G") (pinfunction "G_G") (pintype "bidirectional"))
    )
    (net (code "34") (name "IAT_CPU") (class "Default")
      (node (ref "C10") (pin "1") (pinfunction "1_1") (pintype "passive"))
      (node (ref "D5") (pin "A") (pinfunction "A_A") (pintype "passive"))
      (node (ref "D6") (pin "C") (pinfunction "C_C") (pintype "passive"))
      (node (ref "R40") (pin "2") (pinfunction "2_2") (pintype "passive"))
      (node (ref "U$1") (pin "14/A0") (pinfunction "14/A0_14/A0") (pintype "bidirectional"))
    )
    (net (code "35") (name "IAT_SENSOR") (class "Default")
      (node (ref "C9") (pin "1") (pinfunction "1_1") (pintype "passive"))
      (node (ref "CON1") (pin "12") (pinfunction "12_12") (pintype "passive"))
      (node (ref "R40") (pin "1") (pinfunction "1_1") (pintype "passive"))
      (node (ref "R41") (pin "1") (pinfunction "1_1") (pintype "passive"))
    )
    (net (code "36") (name "IDLE") (class "Default")
      (node (ref "CON1") (pin "16") (pinfunction "16_16") (pintype "passive"))
      (node (ref "U$5") (pin "D") (pinfunction "D_D") (pintype "bidirectional"))
    )
    (net (code "37") (name "IDLE_CPU") (class "Default")
      (node (ref "R16") (pin "2") (pinfunction "2_2") (pintype "passive"))
      (node (ref "U$1") (pin "5") (pinfunction "5_5") (pintype "bidirectional"))
      (node (ref "U$15") (pin "4") (pinfunction "IN_B_4") (pintype "input"))
    )
    (net (code "38") (name "IDLE_TC4") (class "Default")
      (node (ref "R38") (pin "1") (pinfunction "1_1") (pintype "passive"))
      (node (ref "R9") (pin "2") (pinfunction "2_2") (pintype "passive"))
      (node (ref "U$5") (pin "G") (pinfunction "G_G") (pintype "bidirectional"))
    )
    (net (code "39") (name "IGN1") (class "Default")
      (node (ref "CON1") (pin "33") (pinfunction "33_33") (pintype "passive"))
      (node (ref "R68") (pin "2") (pinfunction "2_2") (pintype "passive"))
    )
    (net (code "40") (name "IGN1_CPU") (class "Default")
      (node (ref "R66") (pin "1") (pinfunction "1_1") (pintype "passive"))
      (node (ref "U$1") (pin "29") (pinfunction "29_29") (pintype "bidirectional"))
      (node (ref "U$9") (pin "2") (pinfunction "IN_A_2") (pintype "input"))
    )
    (net (code "41") (name "IGN2") (class "Default")
      (node (ref "CON1") (pin "32") (pinfunction "32_32") (pintype "passive"))
      (node (ref "R67") (pin "2") (pinfunction "2_2") (pintype "passive"))
    )
    (net (code "42") (name "IGN2_CPU") (class "Default")
      (node (ref "R63") (pin "2") (pinfunction "2_2") (pintype "passive"))
      (node (ref "U$1") (pin "30") (pinfunction "30_30") (pintype "bidirectional"))
      (node (ref "U$9") (pin "4") (pinfunction "IN_B_4") (pintype "input"))
    )
    (net (code "43") (name "IGN3") (class "Default")
      (node (ref "CON1") (pin "13") (pinfunction "13_13") (pintype "passive"))
      (node (ref "R36") (pin "2") (pinfunction "2_2") (pintype "passive"))
    )
    (net (code "44") (name "IGN3_CPU") (class "Default")
      (node (ref "R34") (pin "1") (pinfunction "1_1") (pintype "passive"))
      (node (ref "U$1") (pin "31/A12") (pinfunction "31/A12_31/A12") (pintype "bidirectional"))
      (node (ref "U$11") (pin "2") (pinfunction "IN_A_2") (pintype "input"))
    )
    (net (code "45") (name "IGN4") (class "Default")
      (node (ref "CON1") (pin "31") (pinfunction "31_31") (pintype "passive"))
      (node (ref "R35") (pin "2") (pinfunction "2_2") (pintype "passive"))
    )
    (net (code "46") (name "IGN4_CPU") (class "Default")
      (node (ref "R33") (pin "2") (pinfunction "2_2") (pintype "passive"))
      (node (ref "U$1") (pin "32/A13") (pinfunction "32/A13_32/A13") (pintype "bidirectional"))
      (node (ref "U$11") (pin "4") (pinfunction "IN_B_4") (pintype "input"))
    )
    (net (code "47") (name "INJ1_CPU") (class "Default")
      (node (ref "R1") (pin "2") (pinfunction "2_2") (pintype "passive"))
      (node (ref "U$1") (pin "2") (pinfunction "2_2") (pintype "bidirectional"))
      (node (ref "U$14") (pin "2") (pinfunction "IN_A_2") (pintype "input"))
    )
    (net (code "48") (name "INJ1_TC4") (class "Default")
      (node (ref "R3") (pin "1") (pinfunction "1_1") (pintype "passive"))
      (node (ref "R58") (pin "2") (pinfunction "2_2") (pintype "passive"))
      (node (ref "U$12") (pin "G") (pinfunction "G_G") (pintype "bidirectional"))
    )
    (net (code "49") (name "INJ2_CPU") (class "Default")
      (node (ref "R4") (pin "2") (pinfunction "2_2") (pintype "passive"))
      (node (ref "U$1") (pin "10/CS") (pinfunction "10/CS_10/CS") (pintype "bidirectional"))
      (node (ref "U$14") (pin "4") (pinfunction "IN_B_4") (pintype "input"))
    )
    (net (code "50") (name "INJ2_TC4") (class "Default")
      (node (ref "R39") (pin "2") (pinfunction "2_2") (pintype "passive"))
      (node (ref "R5") (pin "1") (pinfunction "1_1") (pintype "passive"))
      (node (ref "U$4") (pin "G") (pinfunction "G_G") (pintype "bidirectional"))
    )
    (net (code "51") (name "INJ3_CPU") (class "Default")
      (node (ref "R7") (pin "2") (pinfunction "2_2") (pintype "passive"))
      (node (ref "U$1") (pin "6") (pinfunction "6_6") (pintype "bidirectional"))
      (node (ref "U$7") (pin "2") (pinfunction "IN_A_2") (pintype "input"))
    )
    (net (code "52") (name "INJ3_TC4") (class "Default")
      (node (ref "R6") (pin "2") (pinfunction "2_2") (pintype "passive"))
      (node (ref "R8") (pin "1") (pinfunction "1_1") (pintype "passive"))
      (node (ref "U$6") (pin "G") (pinfunction "G_G") (pintype "bidirectional"))
    )
    (net (code "53") (name "INJ4_CPU") (class "Default")
      (node (ref "R10") (pin "2") (pinfunction "2_2") (pintype "passive"))
      (node (ref "U$1") (pin "9/CS") (pinfunction "9/CS_9/CS") (pintype "bidirectional"))
      (node (ref "U$7") (pin "4") (pinfunction "IN_B_4") (pintype "input"))
    )
    (net (code "54") (name "INJ4_TC4") (class "Default")
      (node (ref "R11") (pin "1") (pinfunction "1_1") (pintype "passive"))
      (node (ref "R2") (pin "2") (pinfunction "2_2") (pintype "passive"))
      (node (ref "U$8") (pin "G") (pinfunction "G_G") (pintype "bidirectional"))
    )
    (net (code "55") (name "INJECTOR1") (class "Default")
      (node (ref "CON1") (pin "15") (pinfunction "15_15") (pintype "passive"))
      (node (ref "U$12") (pin "D") (pinfunction "D_D") (pintype "bidirectional"))
    )
    (net (code "56") (name "INJECTOR2") (class "Default")
      (node (ref "CON1") (pin "14") (pinfunction "14_14") (pintype "passive"))
      (node (ref "U$4") (pin "D") (pinfunction "D_D") (pintype "bidirectional"))
    )
    (net (code "57") (name "INJECTOR3") (class "Default")
      (node (ref "CON1") (pin "9") (pinfunction "9_9") (pintype "passive"))
      (node (ref "U$6") (pin "D") (pinfunction "D_D") (pintype "bidirectional"))
    )
    (net (code "58") (name "INJECTOR4") (class "Default")
      (node (ref "CON1") (pin "6") (pinfunction "6_6") (pintype "passive"))
      (node (ref "U$8") (pin "D") (pinfunction "D_D") (pintype "bidirectional"))
    )
    (net (code "59") (name "LC1") (class "Default")
      (node (ref "CON1") (pin "2") (pinfunction "2_2") (pintype "passive"))
      (node (ref "Q1") (pin "3") (pinfunction "D_3") (pintype "passive"))
    )
    (net (code "60") (name "LC1_CPU") (class "Default")
      (node (ref "R72") (pin "2") (pinfunction "2_2") (pintype "passive"))
    )
    (net (code "61") (name "MAP_CONV") (class "Default")
      (node (ref "C18") (pin "2") (pinfunction "2_2") (pintype "passive"))
      (node (ref "R31") (pin "2") (pinfunction "2_2") (pintype "passive"))
      (node (ref "R45") (pin "2") (pinfunction "2_2") (pintype "passive"))
    )
    (net (code "62") (name "MAP_CPU") (class "Default")
      (node (ref "IC4") (pin "3") (pinfunction "-IN_3") (pintype "input"))
      (node (ref "IC4") (pin "4") (pinfunction "OUT_4") (pintype "output"))
      (node (ref "U$1") (pin "17/A3") (pinfunction "17/A3_17/A3") (pintype "bidirectional"))
    )
    (net (code "63") (name "Net-(C4-Pad1)") (class "Default")
      (node (ref "C4") (pin "1") (pinfunction "1_1") (pintype "passive"))
      (node (ref "C6") (pin "+") (pinfunction "+_+") (pintype "passive"))
      (node (ref "L2") (pin "1") (pinfunction "1_1") (pintype "passive"))
      (node (ref "STEPSTICK-X") (pin "VMOT") (pinfunction "VMOT_VMOT") (pintype "bidirectional"))
    )
    (net (code "64") (name "Net-(C19-Pad1)") (class "Default")
      (node (ref "C19") (pin "1") (pinfunction "1_1") (pintype "passive"))
      (node (ref "R46") (pin "1") (pinfunction "1_1") (pintype "passive"))
      (node (ref "R47") (pin "2") (pinfunction "2_2") (pintype "passive"))
      (node (ref "R48") (pin "1") (pinfunction "1_1") (pintype "passive"))
    )
    (net (code "65") (name "Net-(D16-PadA)") (class "Default")
      (node (ref "D16") (pin "A") (pinfunction "A_A") (pintype "passive"))
      (node (ref "L1") (pin "1") (pinfunction "1_1") (pintype "passive"))
    )
    (net (code "66") (name "Net-(IC2-FB)") (class "Default")
      (node (ref "C8") (pin "+") (pinfunction "+_+") (pintype "passive"))
      (node (ref "IC2") (pin "4") (pinfunction "FB_4") (pintype "input"))
      (node (ref "L3") (pin "1") (pinfunction "1_1") (pintype "passive"))
      (node (ref "L4") (pin "2") (pinfunction "2_2") (pintype "passive"))
    )
    (net (code "67") (name "Net-(IC2-OUT)") (class "Default")
      (node (ref "D3") (pin "C") (pinfunction "C_C") (pintype "passive"))
      (node (ref "IC2") (pin "2") (pinfunction "OUT_2") (pintype "output"))
      (node (ref "L4") (pin "1") (pinfunction "1_1") (pintype "passive"))
    )
    (net (code "68") (name "Net-(IC4-+IN)") (class "Default")
      (node (ref "IC4") (pin "1") (pinfunction "+IN_1") (pintype "input"))
      (node (ref "R30") (pin "2") (pinfunction "2_2") (pintype "passive"))
      (node (ref "R31") (pin "1") (pinfunction "1_1") (pintype "passive"))
    )
    (net (code "69") (name "Net-(JMP1-Pad3)") (class "Default")
      (node (ref "JMP1") (pin "3") (pinfunction "3_3") (pintype "passive"))
      (node (ref "R53") (pin "2") (pinfunction "2_2") (pintype "passive"))
    )
    (net (code "70") (name "Net-(JMP2-Pad1)") (class "Default")
      (node (ref "JMP2") (pin "1") (pinfunction "1_1") (pintype "passive"))
      (node (ref "R54") (pin "1") (pinfunction "1_1") (pintype "passive"))
    )
    (net (code "71") (name "Net-(LED5-PadA)") (class "Default")
      (node (ref "LED5") (pin "A") (pinfunction "A_A") (pintype "passive"))
      (node (ref "R23") (pin "1") (pinfunction "1_1") (pintype "passive"))
    )
    (net (code "72") (name "Net-(LED6-PadC)") (class "Default")
      (node (ref "LED6") (pin "C") (pinfunction "C_C") (pintype "passive"))
      (node (ref "R64") (pin "2") (pinfunction "2_2") (pintype "passive"))
    )
    (net (code "73") (name "Net-(LED7-PadC)") (class "Default")
      (node (ref "LED7") (pin "C") (pinfunction "C_C") (pintype "passive"))
      (node (ref "R65") (pin "2") (pinfunction "2_2") (pintype "passive"))
    )
    (net (code "74") (name "Net-(PS1-VOUT)") (class "Default")
      (node (ref "C17") (pin "2") (pinfunction "2_2") (pintype "passive"))
      (node (ref "PS1") (pin "4") (pinfunction "VOUT_4") (pintype "output"))
      (node (ref "R45") (pin "1") (pinfunction "1_1") (pintype "passive"))
    )
    (net (code "75") (name "Net-(Q1-G)") (class "Default")
      (node (ref "Q1") (pin "1") (pinfunction "G_1") (pintype "passive"))
      (node (ref "R72") (pin "1") (pinfunction "1_1") (pintype "passive"))
      (node (ref "R73") (pin "1") (pinfunction "1_1") (pintype "passive"))
    )
    (net (code "76") (name "Net-(R25-Pad1)") (class "Default")
      (node (ref "R25") (pin "1") (pinfunction "1_1") (pintype "passive"))
      (node (ref "R60") (pin "2") (pinfunction "2_2") (pintype "passive"))
    )
    (net (code "77") (name "Net-(R25-Pad2)") (class "Default")
      (node (ref "R25") (pin "2") (pinfunction "2_2") (pintype "passive"))
      (node (ref "SJ4") (pin "2") (pinfunction "2_2") (pintype "passive"))
    )
    (net (code "78") (name "Net-(R26-Pad1)") (class "Default")
      (node (ref "R26") (pin "1") (pinfunction "1_1") (pintype "passive"))
      (node (ref "R59") (pin "2") (pinfunction "2_2") (pintype "passive"))
    )
    (net (code "79") (name "Net-(R27-Pad1)") (class "Default")
      (node (ref "R27") (pin "1") (pinfunction "1_1") (pintype "passive"))
      (node (ref "R57") (pin "2") (pinfunction "2_2") (pintype "passive"))
    )
    (net (code "80") (name "Net-(R27-Pad2)") (class "Default")
      (node (ref "R27") (pin "2") (pinfunction "2_2") (pintype "passive"))
      (node (ref "SJ3") (pin "2") (pinfunction "2_2") (pintype "passive"))
    )
    (net (code "81") (name "Net-(R28-Pad2)") (class "Default")
      (node (ref "R28") (pin "2") (pinfunction "2_2") (pintype "passive"))
      (node (ref "R56") (pin "1") (pinfunction "1_1") (pintype "passive"))
    )
    (net (code "82") (name "Net-(R52-Pad2)") (class "Default")
      (node (ref "R52") (pin "2") (pinfunction "2_2") (pintype "passive"))
      (node (ref "R53") (pin "1") (pinfunction "1_1") (pintype "passive"))
      (node (ref "SJ6") (pin "2") (pinfunction "2_2") (pintype "passive"))
    )
    (net (code "83") (name "Net-(R54-Pad2)") (class "Default")
      (node (ref "R54") (pin "2") (pinfunction "2_2") (pintype "passive"))
      (node (ref "R55") (pin "2") (pinfunction "2_2") (pintype "passive"))
      (node (ref "SJ5") (pin "2") (pinfunction "2_2") (pintype "passive"))
    )
    (net (code "84") (name "Net-(STEPSTICK-X-PadRST)") (class "Default")
      (node (ref "STEPSTICK-X") (pin "RST") (pinfunction "RST_RST") (pintype "bidirectional"))
      (node (ref "STEPSTICK-X") (pin "SLP") (pinfunction "SLP_SLP") (pintype "bidirectional"))
    )
    (net (code "85") (name "Net-(U$7-OUT_A)") (class "Default")
      (node (ref "R6") (pin "1") (pinfunction "1_1") (pintype "passive"))
      (node (ref "U$7") (pin "7") (pinfunction "OUT_A_7") (pintype "output"))
    )
    (net (code "86") (name "Net-(U$7-OUT_B)") (class "Default")
      (node (ref "R2") (pin "1") (pinfunction "1_1") (pintype "passive"))
      (node (ref "U$7") (pin "5") (pinfunction "OUT_B_5") (pintype "output"))
    )
    (net (code "87") (name "Net-(U$9-OUT_A)") (class "Default")
      (node (ref "R68") (pin "1") (pinfunction "1_1") (pintype "passive"))
      (node (ref "U$9") (pin "7") (pinfunction "OUT_A_7") (pintype "output"))
    )
    (net (code "88") (name "Net-(U$9-OUT_B)") (class "Default")
      (node (ref "R67") (pin "1") (pinfunction "1_1") (pintype "passive"))
      (node (ref "U$9") (pin "5") (pinfunction "OUT_B_5") (pintype "output"))
    )
    (net (code "89") (name "Net-(U$10-4_COUT1)") (class "Default")
      (node (ref "JMP1") (pin "1") (pinfunction "1_1") (pintype "passive"))
      (node (ref "U$10") (pin "4") (pinfunction "4_COUT1_4") (pintype "bidirectional"))
    )
    (net (code "90") (name "Net-(U$10-5_COUT2)") (class "Default")
      (node (ref "JMP2") (pin "3") (pinfunction "3_3") (pintype "passive"))
      (node (ref "U$10") (pin "5") (pinfunction "5_COUT2_5") (pintype "bidirectional"))
    )
    (net (code "91") (name "Net-(U$10-9_IN2+)") (class "Default")
      (node (ref "C25") (pin "2") (pinfunction "2_2") (pintype "passive"))
      (node (ref "R57") (pin "1") (pinfunction "1_1") (pintype "passive"))
      (node (ref "U$10") (pin "9") (pinfunction "9_IN2+_9") (pintype "bidirectional"))
    )
    (net (code "92") (name "Net-(U$10-10_IN2-)") (class "Default")
      (node (ref "C25") (pin "1") (pinfunction "1_1") (pintype "passive"))
      (node (ref "R28") (pin "1") (pinfunction "1_1") (pintype "passive"))
      (node (ref "U$10") (pin "10") (pinfunction "10_IN2-_10") (pintype "bidirectional"))
    )
    (net (code "93") (name "Net-(U$10-15_IN1-)") (class "Default")
      (node (ref "C26") (pin "2") (pinfunction "2_2") (pintype "passive"))
      (node (ref "R59") (pin "1") (pinfunction "1_1") (pintype "passive"))
      (node (ref "U$10") (pin "15") (pinfunction "15_IN1-_15") (pintype "bidirectional"))
    )
    (net (code "94") (name "Net-(U$10-16_IN1+)") (class "Default")
      (node (ref "C26") (pin "1") (pinfunction "1_1") (pintype "passive"))
      (node (ref "R60") (pin "1") (pinfunction "1_1") (pintype "passive"))
      (node (ref "U$10") (pin "16") (pinfunction "16_IN1+_16") (pintype "bidirectional"))
    )
    (net (code "95") (name "Net-(U$11-OUT_A)") (class "Default")
      (node (ref "R36") (pin "1") (pinfunction "1_1") (pintype "passive"))
      (node (ref "U$11") (pin "7") (pinfunction "OUT_A_7") (pintype "output"))
    )
    (net (code "96") (name "Net-(U$11-OUT_B)") (class "Default")
      (node (ref "R35") (pin "1") (pinfunction "1_1") (pintype "passive"))
      (node (ref "U$11") (pin "5") (pinfunction "OUT_B_5") (pintype "output"))
    )
    (net (code "97") (name "Net-(U$14-OUT_A)") (class "Default")
      (node (ref "R58") (pin "1") (pinfunction "1_1") (pintype "passive"))
      (node (ref "U$14") (pin "7") (pinfunction "OUT_A_7") (pintype "output"))
    )
    (net (code "98") (name "Net-(U$14-OUT_B)") (class "Default")
      (node (ref "R39") (pin "1") (pinfunction "1_1") (pintype "passive"))
      (node (ref "U$14") (pin "5") (pinfunction "OUT_B_5") (pintype "output"))
    )
    (net (code "99") (name "Net-(U$15-OUT_A)") (class "Default")
      (node (ref "R12") (pin "1") (pinfunction "1_1") (pintype "passive"))
      (node (ref "U$15") (pin "7") (pinfunction "OUT_A_7") (pintype "output"))
    )
    (net (code "100") (name "Net-(U$15-OUT_B)") (class "Default")
      (node (ref "R9") (pin "1") (pinfunction "1_1") (pintype "passive"))
      (node (ref "U$15") (pin "5") (pinfunction "OUT_B_5") (pintype "output"))
    )
    (net (code "101") (name "Net-(U$16-OUT_A)") (class "Default")
      (node (ref "R14") (pin "1") (pinfunction "1_1") (pintype "passive"))
      (node (ref "U$16") (pin "7") (pinfunction "OUT_A_7") (pintype "output"))
    )
    (net (code "102") (name "Net-(U$16-OUT_B)") (class "Default")
      (node (ref "R13") (pin "1") (pinfunction "1_1") (pintype "passive"))
      (node (ref "U$16") (pin "5") (pinfunction "OUT_B_5") (pintype "output"))
    )
    (net (code "103") (name "Net-(U$19-OUT_A)") (class "Default")
      (node (ref "R69") (pin "1") (pinfunction "1_1") (pintype "passive"))
      (node (ref "U$19") (pin "7") (pinfunction "OUT_A_7") (pintype "output"))
    )
    (net (code "104") (name "Net-(U$19-OUT_B)") (class "Default")
      (node (ref "R62") (pin "1") (pinfunction "1_1") (pintype "passive"))
      (node (ref "U$19") (pin "5") (pinfunction "OUT_B_5") (pintype "output"))
    )
    (net (code "105") (name "Net-(U1-RS)") (class "Default")
      (node (ref "R22") (pin "1") (pinfunction "1_1") (pintype "passive"))
      (node (ref "U1") (pin "8") (pinfunction "RS_8") (pintype "input"))
    )
    (net (code "106") (name "O2_2_CPU") (class "Default")
      (node (ref "C37") (pin "1") (pinfunction "1_1") (pintype "passive"))
      (node (ref "D15") (pin "A") (pinfunction "A_A") (pintype "passive"))
      (node (ref "D17") (pin "C") (pinfunction "C_C") (pintype "passive"))
      (node (ref "R37") (pin "2") (pinfunction "2_2") (pintype "passive"))
      (node (ref "U$1") (pin "21/DAC0") (pinfunction "A21/DAC0_21/DAC0") (pintype "bidirectional"))
    )
    (net (code "107") (name "O2_2_SENSOR") (class "Default")
      (node (ref "C36") (pin "1") (pinfunction "1_1") (pintype "passive"))
      (node (ref "CON1") (pin "26") (pinfunction "26_26") (pintype "passive"))
      (node (ref "R37") (pin "1") (pinfunction "1_1") (pintype "passive"))
    )
    (net (code "108") (name "O2_CPU") (class "Default")
      (node (ref "C2") (pin "1") (pinfunction "1_1") (pintype "passive"))
      (node (ref "D1") (pin "A") (pinfunction "A_A") (pintype "passive"))
      (node (ref "D2") (pin "C") (pinfunction "C_C") (pintype "passive"))
      (node (ref "R21") (pin "2") (pinfunction "2_2") (pintype "passive"))
      (node (ref "U$1") (pin "A22/DAC1") (pinfunction "A22/DAC1_A22/DAC1") (pintype "bidirectional"))
    )
    (net (code "109") (name "O2_SENSOR") (class "Default")
      (node (ref "C1") (pin "1") (pinfunction "1_1") (pintype "passive"))
      (node (ref "CON1") (pin "8") (pinfunction "8_8") (pintype "passive"))
      (node (ref "R21") (pin "1") (pinfunction "1_1") (pintype "passive"))
    )
    (net (code "110") (name "RST_CPU") (class "Default")
      (node (ref "C21") (pin "1") (pinfunction "1_1") (pintype "passive"))
      (node (ref "D13") (pin "A") (pinfunction "A_A") (pintype "passive"))
      (node (ref "R49") (pin "2") (pinfunction "2_2") (pintype "passive"))
      (node (ref "U$1") (pin "RESET") (pinfunction "RESET_RESET") (pintype "bidirectional"))
    )
    (net (code "111") (name "RX") (class "Default")
      (node (ref "JP1") (pin "3") (pinfunction "3_3") (pintype "passive"))
      (node (ref "U$1") (pin "0/RX") (pinfunction "0/RX_0/RX") (pintype "bidirectional"))
    )
    (net (code "112") (name "STEP_1A") (class "Default")
      (node (ref "CON1") (pin "36") (pinfunction "36_36") (pintype "passive"))
      (node (ref "STEPSTICK-X") (pin "1A") (pinfunction "1A_1A") (pintype "bidirectional"))
    )
    (net (code "113") (name "STEP_1B") (class "Default")
      (node (ref "CON1") (pin "17") (pinfunction "17_17") (pintype "passive"))
      (node (ref "STEPSTICK-X") (pin "1B") (pinfunction "1B_1B") (pintype "bidirectional"))
    )
    (net (code "114") (name "STEP_2A") (class "Default")
      (node (ref "CON1") (pin "35") (pinfunction "35_35") (pintype "passive"))
      (node (ref "STEPSTICK-X") (pin "2A") (pinfunction "2A_2A") (pintype "bidirectional"))
    )
    (net (code "115") (name "STEP_2B") (class "Default")
      (node (ref "CON1") (pin "34") (pinfunction "34_34") (pintype "passive"))
      (node (ref "STEPSTICK-X") (pin "2B") (pinfunction "2B_2B") (pintype "bidirectional"))
    )
    (net (code "116") (name "STP") (class "Default")
      (node (ref "STEPSTICK-X") (pin "SPT") (pinfunction "STEP_SPT") (pintype "bidirectional"))
      (node (ref "U$1") (pin "35/A16") (pinfunction "35/A16_35/A16") (pintype "bidirectional"))
    )
    (net (code "117") (name "TPS_CPU") (class "Default")
      (node (ref "C14") (pin "1") (pinfunction "1_1") (pintype "passive"))
      (node (ref "D10") (pin "C") (pinfunction "C_C") (pintype "passive"))
      (node (ref "D9") (pin "A") (pinfunction "A_A") (pintype "passive"))
      (node (ref "R44") (pin "2") (pinfunction "2_2") (pintype "passive"))
      (node (ref "U$1") (pin "16/A2") (pinfunction "16/A2_16/A2") (pintype "bidirectional"))
    )
    (net (code "118") (name "TPS_SIGNAL") (class "Default")
      (node (ref "C13") (pin "1") (pinfunction "1_1") (pintype "passive"))
      (node (ref "CON1") (pin "27") (pinfunction "27_27") (pintype "passive"))
      (node (ref "R44") (pin "1") (pinfunction "1_1") (pintype "passive"))
    )
    (net (code "119") (name "TX") (class "Default")
      (node (ref "JP1") (pin "4") (pinfunction "4_4") (pintype "passive"))
      (node (ref "U$1") (pin "1/TX") (pinfunction "1/TX_1/TX") (pintype "bidirectional"))
    )
    (net (code "120") (name "VIN") (class "Default")
      (node (ref "CON1") (pin "19") (pinfunction "19_19") (pintype "passive"))
      (node (ref "CON1") (pin "37") (pinfunction "37_37") (pintype "passive"))
      (node (ref "L1") (pin "2") (pinfunction "2_2") (pintype "passive"))
    )
    (net (code "121") (name "VR1+") (class "Default")
      (node (ref "CON1") (pin "30") (pinfunction "30_30") (pintype "passive"))
      (node (ref "R29") (pin "1") (pinfunction "1_1") (pintype "passive"))
      (node (ref "SJ4") (pin "1") (pinfunction "1_1") (pintype "passive"))
      (node (ref "SJ6") (pin "1") (pinfunction "1_1") (pintype "passive"))
    )
    (net (code "122") (name "VR1-") (class "Default")
      (node (ref "CON1") (pin "11") (pinfunction "11_11") (pintype "passive"))
      (node (ref "R26") (pin "2") (pinfunction "2_2") (pintype "passive"))
      (node (ref "R29") (pin "2") (pinfunction "2_2") (pintype "passive"))
    )
    (net (code "123") (name "VR2+") (class "Default")
      (node (ref "CON1") (pin "10") (pinfunction "10_10") (pintype "passive"))
      (node (ref "R32") (pin "2") (pinfunction "2_2") (pintype "passive"))
      (node (ref "SJ3") (pin "1") (pinfunction "1_1") (pintype "passive"))
      (node (ref "SJ5") (pin "1") (pinfunction "1_1") (pintype "passive"))
    )
    (net (code "124") (name "VR2-") (class "Default")
      (node (ref "CON1") (pin "28") (pinfunction "28_28") (pintype "passive"))
      (node (ref "R32") (pin "1") (pinfunction "1_1") (pintype "passive"))
      (node (ref "R56") (pin "2") (pinfunction "2_2") (pintype "passive"))
    )
    (net (code "125") (name "unconnected-(CON1-Pad21)") (class "Default")
      (node (ref "CON1") (pin "21") (pinfunction "21_21") (pintype "passive"))
    )
    (net (code "126") (name "unconnected-(PS1-NC-Pad1)") (class "Default")
      (node (ref "PS1") (pin "1") (pinfunction "NC_1") (pintype "no_connect"))
    )
    (net (code "127") (name "unconnected-(PS1-NC-Pad5)") (class "Default")
      (node (ref "PS1") (pin "5") (pinfunction "NC_5") (pintype "no_connect"))
    )
    (net (code "128") (name "unconnected-(PS1-NC-Pad6)") (class "Default")
      (node (ref "PS1") (pin "6") (pinfunction "NC_6") (pintype "no_connect"))
    )
    (net (code "129") (name "unconnected-(STEPSTICK-X-PadEN)") (class "Default")
      (node (ref "STEPSTICK-X") (pin "EN") (pinfunction "EN_EN") (pintype "bidirectional"))
    )
    (net (code "130") (name "unconnected-(STEPSTICK-X-PadMS1)") (class "Default")
      (node (ref "STEPSTICK-X") (pin "MS1") (pinfunction "MS1_MS1") (pintype "bidirectional"))
    )
    (net (code "131") (name "unconnected-(STEPSTICK-X-PadMS2)") (class "Default")
      (node (ref "STEPSTICK-X") (pin "MS2") (pinfunction "MS2_MS2") (pintype "bidirectional"))
    )
    (net (code "132") (name "unconnected-(STEPSTICK-X-PadMS3)") (class "Default")
      (node (ref "STEPSTICK-X") (pin "MS3") (pinfunction "MS3_MS3") (pintype "bidirectional"))
    )
    (net (code "133") (name "unconnected-(U$1-Pad3V3)") (class "Default")
      (node (ref "U$1") (pin "3V3") (pinfunction "3V3_3V3") (pintype "bidirectional"))
    )
    (net (code "134") (name "unconnected-(U$1-Pad3V3_2)") (class "Default")
      (node (ref "U$1") (pin "3V3_2") (pinfunction "3V3_2_3V3_2") (pintype "bidirectional"))
    )
    (net (code "135") (name "unconnected-(U$1-Pad12{slash}MISO)") (class "Default")
      (node (ref "U$1") (pin "12/MISO") (pinfunction "12/MISO_12/MISO") (pintype "bidirectional"))
    )
    (net (code "136") (name "unconnected-(U$1-Pad13{slash}SCK)") (class "Default")
      (node (ref "U$1") (pin "13/SCK") (pinfunction "13/SCK_13/SCK") (pintype "bidirectional"))
    )
    (net (code "137") (name "unconnected-(U$1-Pad19{slash}A5{slash}SCL)") (class "Default")
      (node (ref "U$1") (pin "19/A5/SCL") (pinfunction "19/A5/SCL_19/A5/SCL") (pintype "bidirectional"))
    )
    (net (code "138") (name "unconnected-(U$1-Pad20{slash}A6)") (class "Default")
      (node (ref "U$1") (pin "20/A6") (pinfunction "20/A6_20/A6") (pintype "bidirectional"))
    )
    (net (code "139") (name "unconnected-(U$1-Pad21{slash}A7)") (class "Default")
      (node (ref "U$1") (pin "21/A7") (pinfunction "21/A7_21/A7") (pintype "bidirectional"))
    )
    (net (code "140") (name "unconnected-(U$1-Pad22{slash}A8)") (class "Default")
      (node (ref "U$1") (pin "22/A8") (pinfunction "22/A8_22/A8") (pintype "bidirectional"))
    )
    (net (code "141") (name "unconnected-(U$1-Pad24)") (class "Default")
      (node (ref "U$1") (pin "24") (pinfunction "24_24") (pintype "bidirectional"))
    )
    (net (code "142") (name "unconnected-(U$1-Pad25)") (class "Default")
      (node (ref "U$1") (pin "25") (pinfunction "25_25") (pintype "bidirectional"))
    )
    (net (code "143") (name "unconnected-(U$1-Pad26)") (class "Default")
      (node (ref "U$1") (pin "26") (pinfunction "26_26") (pintype "bidirectional"))
    )
    (net (code "144") (name "unconnected-(U$1-Pad27)") (class "Default")
      (node (ref "U$1") (pin "27") (pinfunction "27_27") (pintype "bidirectional"))
    )
    (net (code "145") (name "unconnected-(U$1-Pad28)") (class "Default")
      (node (ref "U$1") (pin "28") (pinfunction "28_28") (pintype "bidirectional"))
    )
    (net (code "146") (name "unconnected-(U$1-Pad33{slash}A14)") (class "Default")
      (node (ref "U$1") (pin "33/A14") (pinfunction "33/A14_33/A14") (pintype "bidirectional"))
    )
    (net (code "147") (name "unconnected-(U$1-Pad39{slash}A20)") (class "Default")
      (node (ref "U$1") (pin "39/A20") (pinfunction "39/A20_39/A20") (pintype "bidirectional"))
    )
    (net (code "148") (name "unconnected-(U$1-PadAGND)") (class "Default")
      (node (ref "U$1") (pin "AGND") (pinfunction "AGND_AGND") (pintype "bidirectional"))
    )
    (net (code "149") (name "unconnected-(U$1-PadAREF)") (class "Default")
      (node (ref "U$1") (pin "AREF") (pinfunction "AREF_AREF") (pintype "bidirectional"))
    )
    (net (code "150") (name "unconnected-(U$1-PadGND2)") (class "Default")
      (node (ref "U$1") (pin "GND2") (pinfunction "GND2_GND2") (pintype "bidirectional"))
    )
    (net (code "151") (name "unconnected-(U$1-PadGND3)") (class "Default")
      (node (ref "U$1") (pin "GND3") (pinfunction "GND3_GND3") (pintype "bidirectional"))
    )
    (net (code "152") (name "unconnected-(U$1-PadPROG)") (class "Default")
      (node (ref "U$1") (pin "PROG") (pinfunction "PROG_PROG") (pintype "bidirectional"))
    )
    (net (code "153") (name "unconnected-(U$1-PadU5V)") (class "Default")
      (node (ref "U$1") (pin "U5V") (pinfunction "U5V_U5V") (pintype "bidirectional"))
    )
    (net (code "154") (name "unconnected-(U$1-PadUD+)") (class "Default")
      (node (ref "U$1") (pin "UD+") (pinfunction "UD+_UD+") (pintype "bidirectional"))
    )
    (net (code "155") (name "unconnected-(U$1-PadUD-)") (class "Default")
      (node (ref "U$1") (pin "UD-") (pinfunction "UD-_UD-") (pintype "bidirectional"))
    )
    (net (code "156") (name "unconnected-(U$1-PadUGND1)") (class "Default")
      (node (ref "U$1") (pin "UGND1") (pinfunction "UGND1_UGND1") (pintype "bidirectional"))
    )
    (net (code "157") (name "unconnected-(U$1-PadUGND2)") (class "Default")
      (node (ref "U$1") (pin "UGND2") (pinfunction "UGND2_UGND2") (pintype "bidirectional"))
    )
    (net (code "158") (name "unconnected-(U$1-PadVBAT)") (class "Default")
      (node (ref "U$1") (pin "VBAT") (pinfunction "VBAT_VBAT") (pintype "bidirectional"))
    )
    (net (code "159") (name "unconnected-(U$1-PadVUSB)") (class "Default")
      (node (ref "U$1") (pin "VUSB") (pinfunction "VUSB_VUSB") (pintype "bidirectional"))
    )
    (net (code "160") (name "unconnected-(U$7-NC-Pad1)") (class "Default")
      (node (ref "U$7") (pin "1") (pinfunction "NC_1") (pintype "no_connect"))
    )
    (net (code "161") (name "unconnected-(U$7-NC-Pad8)") (class "Default")
      (node (ref "U$7") (pin "8") (pinfunction "NC_8") (pintype "no_connect"))
    )
    (net (code "162") (name "unconnected-(U$9-NC-Pad1)") (class "Default")
      (node (ref "U$9") (pin "1") (pinfunction "NC_1") (pintype "no_connect"))
    )
    (net (code "163") (name "unconnected-(U$9-NC-Pad8)") (class "Default")
      (node (ref "U$9") (pin "8") (pinfunction "NC_8") (pintype "no_connect"))
    )
    (net (code "164") (name "unconnected-(U$10-2_EXT1-Pad2)") (class "Default")
      (node (ref "U$10") (pin "2") (pinfunction "2_EXT1_2") (pintype "bidirectional"))
    )
    (net (code "165") (name "unconnected-(U$10-7_EXT2-Pad7)") (class "Default")
      (node (ref "U$10") (pin "7") (pinfunction "7_EXT2_7") (pintype "bidirectional"))
    )
    (net (code "166") (name "unconnected-(U$10-12_DIRN-Pad12)") (class "Default")
      (node (ref "U$10") (pin "12") (pinfunction "12_DIRN_12") (pintype "bidirectional"))
    )
    (net (code "167") (name "unconnected-(U$11-NC-Pad1)") (class "Default")
      (node (ref "U$11") (pin "1") (pinfunction "NC_1") (pintype "no_connect"))
    )
    (net (code "168") (name "unconnected-(U$11-NC-Pad8)") (class "Default")
      (node (ref "U$11") (pin "8") (pinfunction "NC_8") (pintype "no_connect"))
    )
    (net (code "169") (name "unconnected-(U$14-NC-Pad1)") (class "Default")
      (node (ref "U$14") (pin "1") (pinfunction "NC_1") (pintype "no_connect"))
    )
    (net (code "170") (name "unconnected-(U$14-NC-Pad8)") (class "Default")
      (node (ref "U$14") (pin "8") (pinfunction "NC_8") (pintype "no_connect"))
    )
    (net (code "171") (name "unconnected-(U$15-NC-Pad1)") (class "Default")
      (node (ref "U$15") (pin "1") (pinfunction "NC_1") (pintype "no_connect"))
    )
    (net (code "172") (name "unconnected-(U$15-NC-Pad8)") (class "Default")
      (node (ref "U$15") (pin "8") (pinfunction "NC_8") (pintype "no_connect"))
    )
    (net (code "173") (name "unconnected-(U$16-NC-Pad1)") (class "Default")
      (node (ref "U$16") (pin "1") (pinfunction "NC_1") (pintype "no_connect"))
    )
    (net (code "174") (name "unconnected-(U$16-NC-Pad8)") (class "Default")
      (node (ref "U$16") (pin "8") (pinfunction "NC_8") (pintype "no_connect"))
    )
    (net (code "175") (name "unconnected-(U$19-NC-Pad1)") (class "Default")
      (node (ref "U$19") (pin "1") (pinfunction "NC_1") (pintype "no_connect"))
    )
    (net (code "176") (name "unconnected-(U$19-NC-Pad8)") (class "Default")
      (node (ref "U$19") (pin "8") (pinfunction "NC_8") (pintype "no_connect"))
    )
    (net (code "177") (name "unconnected-(U1-VREF-Pad5)") (class "Default")
      (node (ref "U1") (pin "5") (pinfunction "VREF_5") (pintype "output"))
    )
  )
)
